# keyboard.net
KiCad netlist of a schematic drawn in Altium Designer
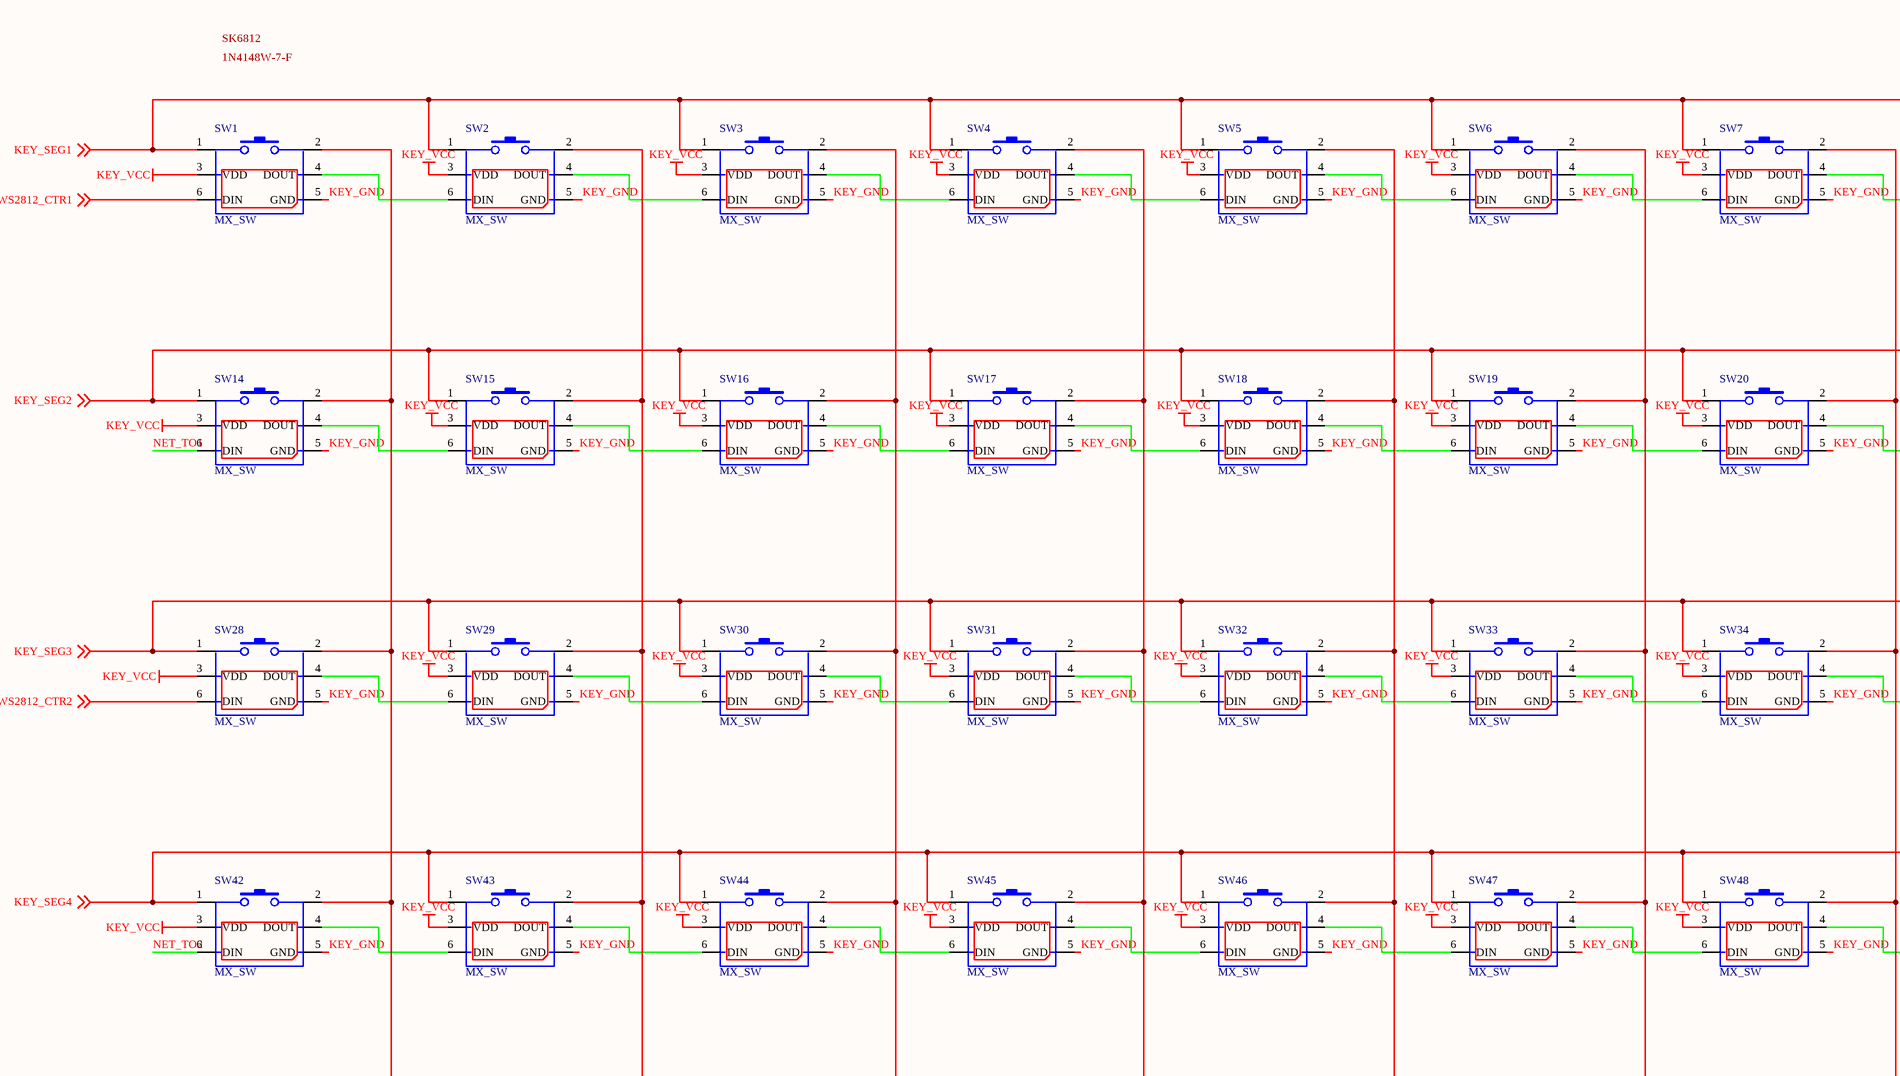
[diagram p0: keyboard.SchDoc, top left]
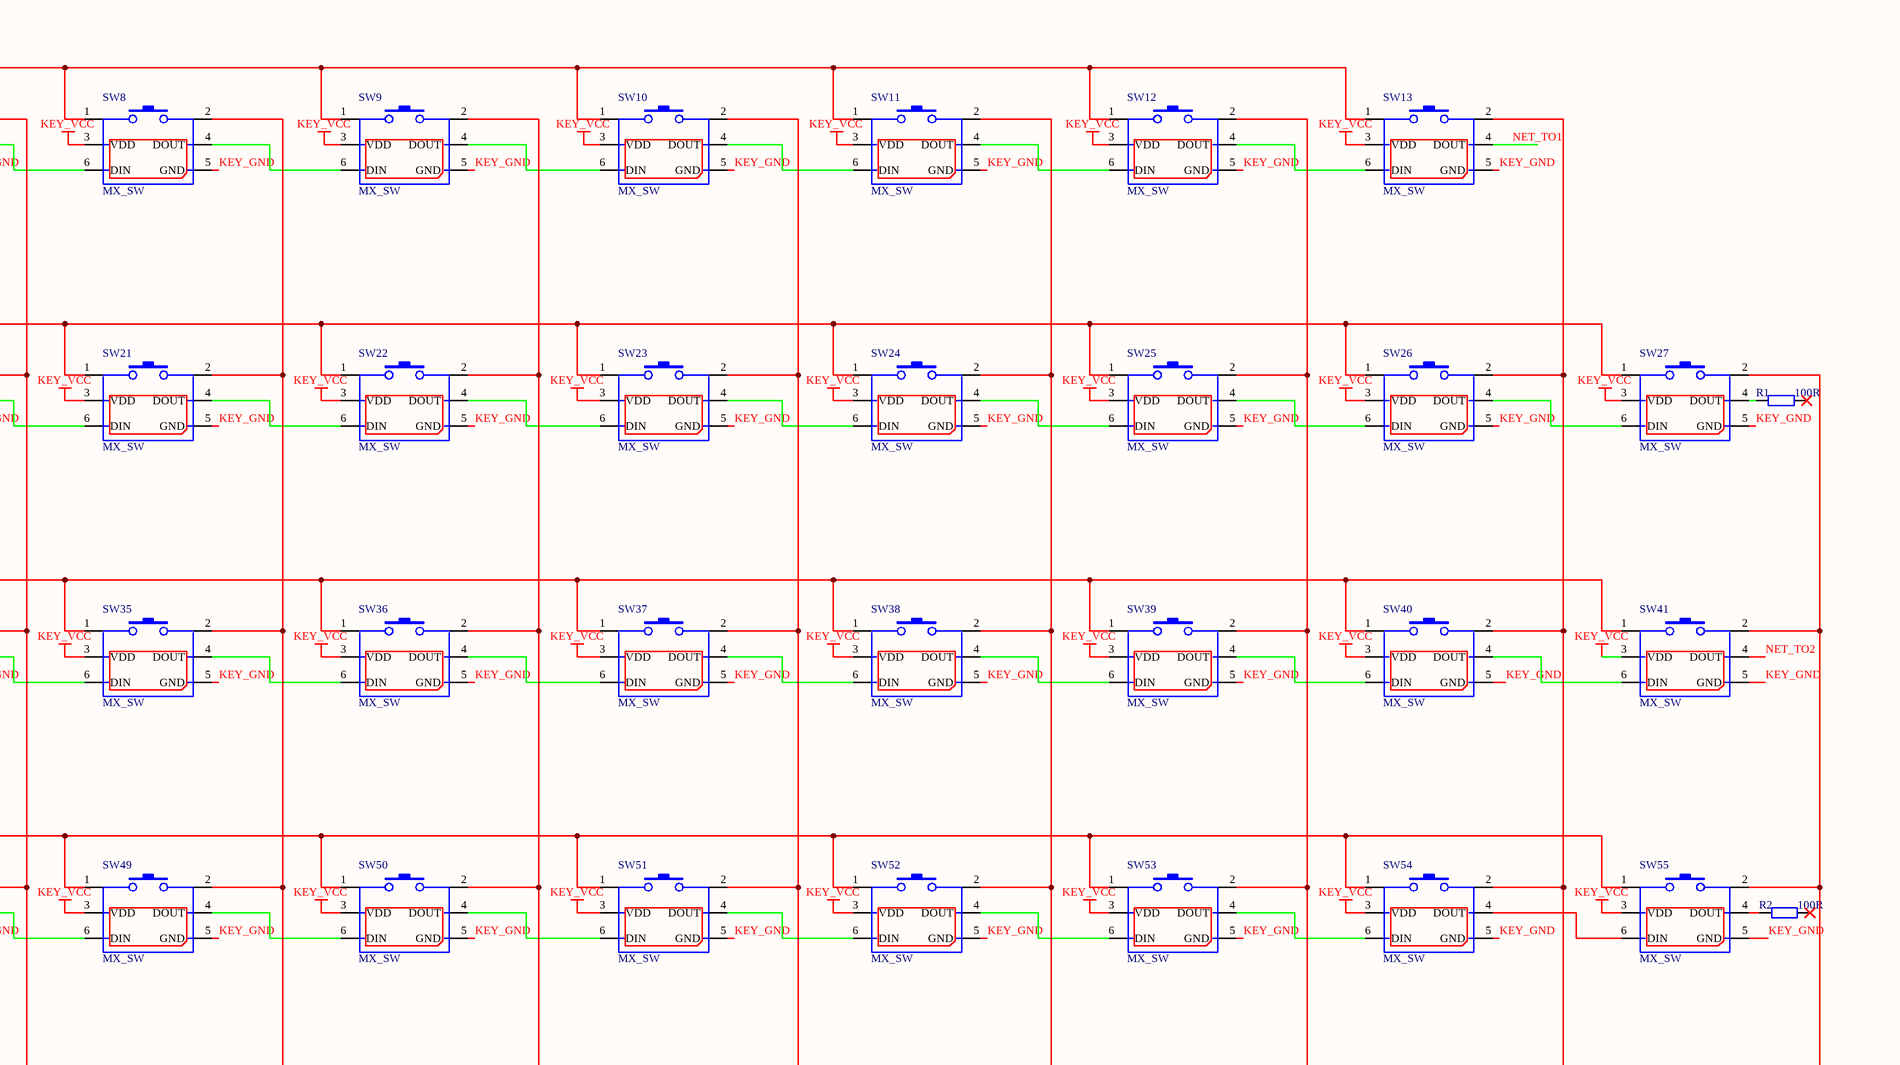
[diagram p1: keyboard.SchDoc, top right]
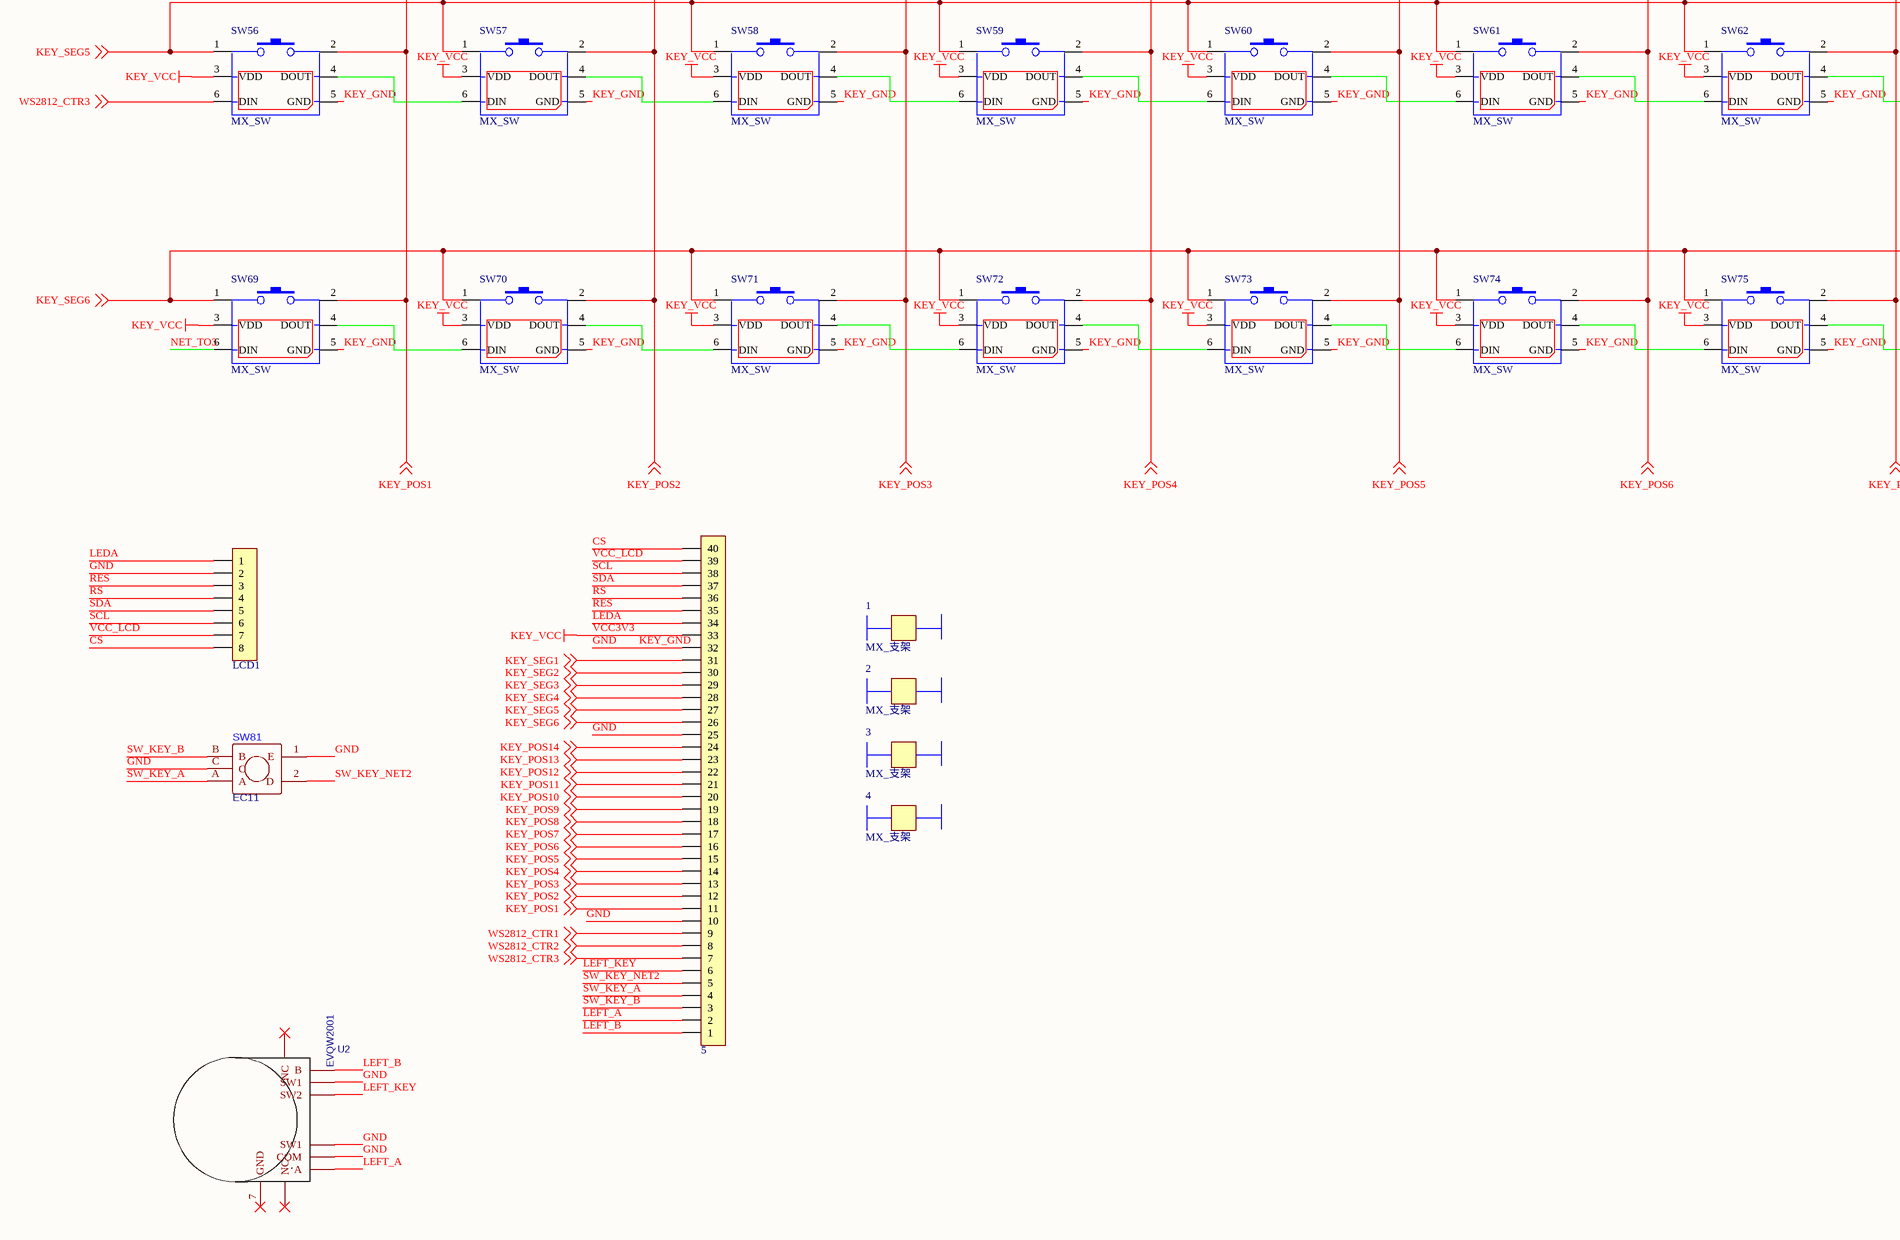
[diagram p2: keyboard.SchDoc, bottom left]
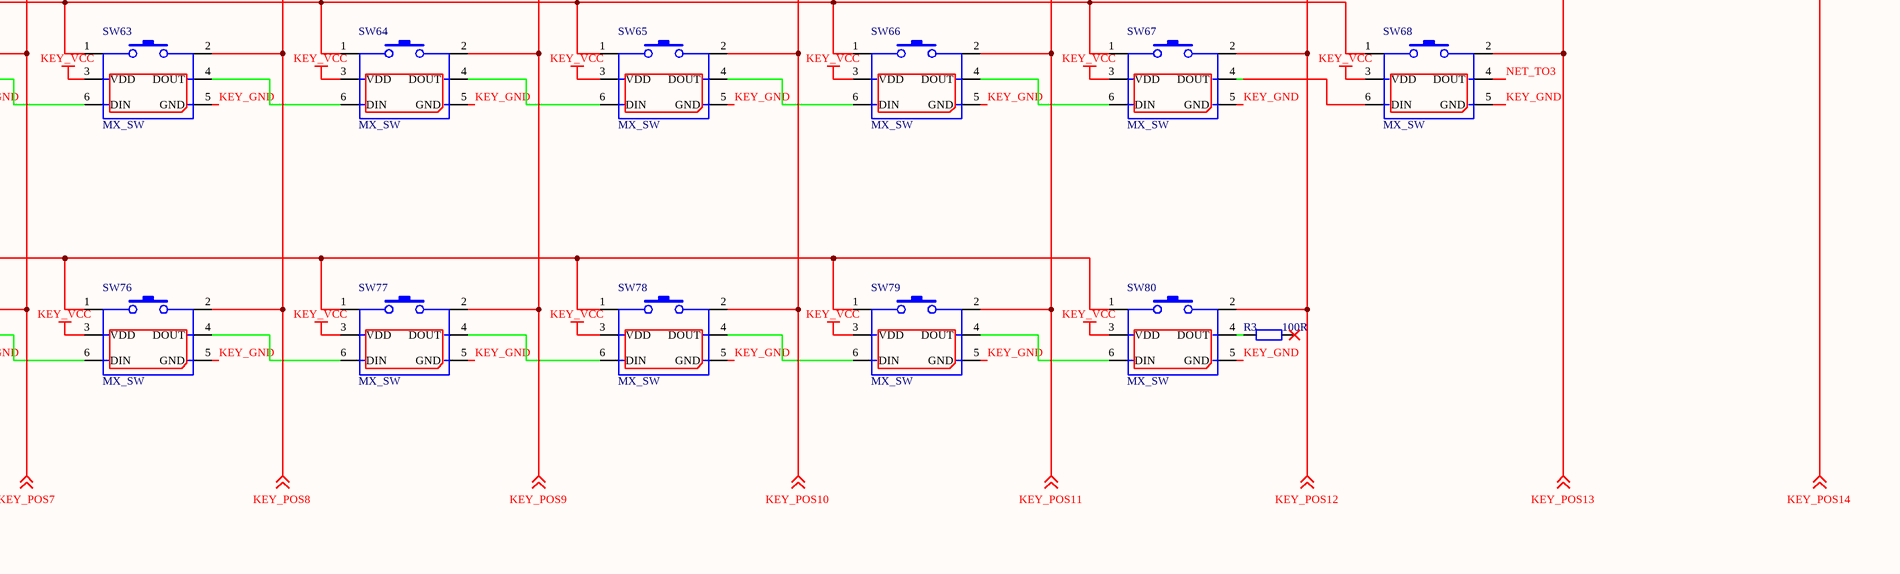
[diagram p3: keyboard.SchDoc, bottom right]

(export (version "E")
  (design (tool "Eeschema 10.0.6"))
  (components
    (comp (ref "1") (value "MX_支架") (footprint "1x2") (libsource (lib "机械键盘") (part "MX_支架")))
    (comp (ref "2") (value "MX_支架") (footprint "1x2") (libsource (lib "机械键盘") (part "MX_支架")))
    (comp (ref "3") (value "MX_支架") (footprint "1x2") (libsource (lib "机械键盘") (part "MX_支架")))
    (comp (ref "4") (value "MX_支架") (footprint "1x2") (libsource (lib "机械键盘") (part "MX_支架")))
    (comp (ref "5")
      (value "FPC1.0-40P")
      (footprint "FPC0.5 2H-WS-40P")
      (description "FPC连接器")
      (fields (field (name "版权归属") "黎明电子style"))
      (libsource (lib "FPC连接器") (part "FPC-40P"))
    )
    (comp (ref "LCD1")
      (value "FPC1.0-8P")
      (footprint "FPC0.5 2H-WS-8P")
      (description "FPC连接器")
      (fields (field (name "版权归属") "黎明电子style"))
      (libsource (lib "FPC连接器") (part "FPC-8P"))
    )
    (comp (ref "R1")
      (value "100R")
      (footprint "R 0805_M")
      (description "贴片电阻")
      (libsource (lib "0.1 - 电阻-电容-电感") (part "R"))
    )
    (comp (ref "R2")
      (value "100R")
      (footprint "R 0805_M")
      (description "贴片电阻")
      (libsource (lib "0.1 - 电阻-电容-电感") (part "R"))
    )
    (comp (ref "R3")
      (value "100R")
      (footprint "R 0805_M")
      (description "贴片电阻")
      (libsource (lib "0.1 - 电阻-电容-电感") (part "R"))
    )
    (comp (ref "SW1")
      (value "MX_SW")
      (footprint "MX_G_Pro")
      (description "with Fixation pins  1-Pole w/Diode")
      (libsource (lib "机械键盘") (part "MX_SW-7"))
    )
    (comp (ref "SW2")
      (value "MX_SW")
      (footprint "MX_G_Pro")
      (description "with Fixation pins  1-Pole w/Diode")
      (libsource (lib "机械键盘") (part "MX_SW-7"))
    )
    (comp (ref "SW3")
      (value "MX_SW")
      (footprint "MX_G_Pro")
      (description "with Fixation pins  1-Pole w/Diode")
      (libsource (lib "机械键盘") (part "MX_SW-7"))
    )
    (comp (ref "SW4")
      (value "MX_SW")
      (footprint "MX_G_Pro")
      (description "with Fixation pins  1-Pole w/Diode")
      (libsource (lib "机械键盘") (part "MX_SW-7"))
    )
    (comp (ref "SW5")
      (value "MX_SW")
      (footprint "MX_G_Pro")
      (description "with Fixation pins  1-Pole w/Diode")
      (libsource (lib "机械键盘") (part "MX_SW-7"))
    )
    (comp (ref "SW6")
      (value "MX_SW")
      (footprint "MX_G_Pro")
      (description "with Fixation pins  1-Pole w/Diode")
      (libsource (lib "机械键盘") (part "MX_SW-7"))
    )
    (comp (ref "SW7")
      (value "MX_SW")
      (footprint "MX_G_Pro")
      (description "with Fixation pins  1-Pole w/Diode")
      (libsource (lib "机械键盘") (part "MX_SW-7"))
    )
    (comp (ref "SW8")
      (value "MX_SW")
      (footprint "MX_G_Pro")
      (description "with Fixation pins  1-Pole w/Diode")
      (libsource (lib "机械键盘") (part "MX_SW-7"))
    )
    (comp (ref "SW9")
      (value "MX_SW")
      (footprint "MX_G_Pro")
      (description "with Fixation pins  1-Pole w/Diode")
      (libsource (lib "机械键盘") (part "MX_SW-7"))
    )
    (comp (ref "SW10")
      (value "MX_SW")
      (footprint "MX_G_Pro")
      (description "with Fixation pins  1-Pole w/Diode")
      (libsource (lib "机械键盘") (part "MX_SW-7"))
    )
    (comp (ref "SW11")
      (value "MX_SW")
      (footprint "MX_G_Pro")
      (description "with Fixation pins  1-Pole w/Diode")
      (libsource (lib "机械键盘") (part "MX_SW-7"))
    )
    (comp (ref "SW12")
      (value "MX_SW")
      (footprint "MX_G_Pro")
      (description "with Fixation pins  1-Pole w/Diode")
      (libsource (lib "机械键盘") (part "MX_SW-7"))
    )
    (comp (ref "SW13")
      (value "MX_SW")
      (footprint "MX_G_Pro")
      (description "with Fixation pins  1-Pole w/Diode")
      (libsource (lib "机械键盘") (part "MX_SW-7"))
    )
    (comp (ref "SW14")
      (value "MX_SW")
      (footprint "MX_G_Pro")
      (description "with Fixation pins  1-Pole w/Diode")
      (libsource (lib "机械键盘") (part "MX_SW-7"))
    )
    (comp (ref "SW15")
      (value "MX_SW")
      (footprint "MX_G_Pro")
      (description "with Fixation pins  1-Pole w/Diode")
      (libsource (lib "机械键盘") (part "MX_SW-7"))
    )
    (comp (ref "SW16")
      (value "MX_SW")
      (footprint "MX_G_Pro")
      (description "with Fixation pins  1-Pole w/Diode")
      (libsource (lib "机械键盘") (part "MX_SW-7"))
    )
    (comp (ref "SW17")
      (value "MX_SW")
      (footprint "MX_G_Pro")
      (description "with Fixation pins  1-Pole w/Diode")
      (libsource (lib "机械键盘") (part "MX_SW-7"))
    )
    (comp (ref "SW18")
      (value "MX_SW")
      (footprint "MX_G_Pro")
      (description "with Fixation pins  1-Pole w/Diode")
      (libsource (lib "机械键盘") (part "MX_SW-7"))
    )
    (comp (ref "SW19")
      (value "MX_SW")
      (footprint "MX_G_Pro")
      (description "with Fixation pins  1-Pole w/Diode")
      (libsource (lib "机械键盘") (part "MX_SW-7"))
    )
    (comp (ref "SW20")
      (value "MX_SW")
      (footprint "MX_G_Pro")
      (description "with Fixation pins  1-Pole w/Diode")
      (libsource (lib "机械键盘") (part "MX_SW-7"))
    )
    (comp (ref "SW21")
      (value "MX_SW")
      (footprint "MX_G_Pro")
      (description "with Fixation pins  1-Pole w/Diode")
      (libsource (lib "机械键盘") (part "MX_SW-7"))
    )
    (comp (ref "SW22")
      (value "MX_SW")
      (footprint "MX_G_Pro")
      (description "with Fixation pins  1-Pole w/Diode")
      (libsource (lib "机械键盘") (part "MX_SW-7"))
    )
    (comp (ref "SW23")
      (value "MX_SW")
      (footprint "MX_G_Pro")
      (description "with Fixation pins  1-Pole w/Diode")
      (libsource (lib "机械键盘") (part "MX_SW-7"))
    )
    (comp (ref "SW24")
      (value "MX_SW")
      (footprint "MX_G_Pro")
      (description "with Fixation pins  1-Pole w/Diode")
      (libsource (lib "机械键盘") (part "MX_SW-7"))
    )
    (comp (ref "SW25")
      (value "MX_SW")
      (footprint "MX_G_Pro")
      (description "with Fixation pins  1-Pole w/Diode")
      (libsource (lib "机械键盘") (part "MX_SW-7"))
    )
    (comp (ref "SW26")
      (value "MX_SW")
      (footprint "MX_G_Pro")
      (description "with Fixation pins  1-Pole w/Diode")
      (libsource (lib "机械键盘") (part "MX_SW-7"))
    )
    (comp (ref "SW27")
      (value "MX_SW")
      (footprint "MX_G_Pro_Backspace")
      (description "with Fixation pins  1-Pole w/Diode")
      (libsource (lib "机械键盘") (part "MX_SW-7"))
    )
    (comp (ref "SW28")
      (value "MX_SW")
      (footprint "MX_G_Pro_MX_Tab")
      (description "with Fixation pins  1-Pole w/Diode")
      (libsource (lib "机械键盘") (part "MX_SW-7"))
    )
    (comp (ref "SW29")
      (value "MX_SW")
      (footprint "MX_G_Pro")
      (description "with Fixation pins  1-Pole w/Diode")
      (libsource (lib "机械键盘") (part "MX_SW-7"))
    )
    (comp (ref "SW30")
      (value "MX_SW")
      (footprint "MX_G_Pro")
      (description "with Fixation pins  1-Pole w/Diode")
      (libsource (lib "机械键盘") (part "MX_SW-7"))
    )
    (comp (ref "SW31")
      (value "MX_SW")
      (footprint "MX_G_Pro")
      (description "with Fixation pins  1-Pole w/Diode")
      (libsource (lib "机械键盘") (part "MX_SW-7"))
    )
    (comp (ref "SW32")
      (value "MX_SW")
      (footprint "MX_G_Pro")
      (description "with Fixation pins  1-Pole w/Diode")
      (libsource (lib "机械键盘") (part "MX_SW-7"))
    )
    (comp (ref "SW33")
      (value "MX_SW")
      (footprint "MX_G_Pro")
      (description "with Fixation pins  1-Pole w/Diode")
      (libsource (lib "机械键盘") (part "MX_SW-7"))
    )
    (comp (ref "SW34")
      (value "MX_SW")
      (footprint "MX_G_Pro")
      (description "with Fixation pins  1-Pole w/Diode")
      (libsource (lib "机械键盘") (part "MX_SW-7"))
    )
    (comp (ref "SW35")
      (value "MX_SW")
      (footprint "MX_G_Pro")
      (description "with Fixation pins  1-Pole w/Diode")
      (libsource (lib "机械键盘") (part "MX_SW-7"))
    )
    (comp (ref "SW36")
      (value "MX_SW")
      (footprint "MX_G_Pro")
      (description "with Fixation pins  1-Pole w/Diode")
      (libsource (lib "机械键盘") (part "MX_SW-7"))
    )
    (comp (ref "SW37")
      (value "MX_SW")
      (footprint "MX_G_Pro")
      (description "with Fixation pins  1-Pole w/Diode")
      (libsource (lib "机械键盘") (part "MX_SW-7"))
    )
    (comp (ref "SW38")
      (value "MX_SW")
      (footprint "MX_G_Pro")
      (description "with Fixation pins  1-Pole w/Diode")
      (libsource (lib "机械键盘") (part "MX_SW-7"))
    )
    (comp (ref "SW39")
      (value "MX_SW")
      (footprint "MX_G_Pro")
      (description "with Fixation pins  1-Pole w/Diode")
      (libsource (lib "机械键盘") (part "MX_SW-7"))
    )
    (comp (ref "SW40")
      (value "MX_SW")
      (footprint "MX_G_Pro")
      (description "with Fixation pins  1-Pole w/Diode")
      (libsource (lib "机械键盘") (part "MX_SW-7"))
    )
    (comp (ref "SW41")
      (value "MX_SW")
      (footprint "MX_G_Pro_MX_Tab")
      (description "with Fixation pins  1-Pole w/Diode")
      (libsource (lib "机械键盘") (part "MX_SW-7"))
    )
    (comp (ref "SW42")
      (value "MX_SW")
      (footprint "MX_G_Pro_CapsLock")
      (description "with Fixation pins  1-Pole w/Diode")
      (libsource (lib "机械键盘") (part "MX_SW-7"))
    )
    (comp (ref "SW43")
      (value "MX_SW")
      (footprint "MX_G_Pro")
      (description "with Fixation pins  1-Pole w/Diode")
      (libsource (lib "机械键盘") (part "MX_SW-7"))
    )
    (comp (ref "SW44")
      (value "MX_SW")
      (footprint "MX_G_Pro")
      (description "with Fixation pins  1-Pole w/Diode")
      (libsource (lib "机械键盘") (part "MX_SW-7"))
    )
    (comp (ref "SW45")
      (value "MX_SW")
      (footprint "MX_G_Pro")
      (description "with Fixation pins  1-Pole w/Diode")
      (libsource (lib "机械键盘") (part "MX_SW-7"))
    )
    (comp (ref "SW46")
      (value "MX_SW")
      (footprint "MX_G_Pro")
      (description "with Fixation pins  1-Pole w/Diode")
      (libsource (lib "机械键盘") (part "MX_SW-7"))
    )
    (comp (ref "SW47")
      (value "MX_SW")
      (footprint "MX_G_Pro")
      (description "with Fixation pins  1-Pole w/Diode")
      (libsource (lib "机械键盘") (part "MX_SW-7"))
    )
    (comp (ref "SW48")
      (value "MX_SW")
      (footprint "MX_G_Pro")
      (description "with Fixation pins  1-Pole w/Diode")
      (libsource (lib "机械键盘") (part "MX_SW-7"))
    )
    (comp (ref "SW49")
      (value "MX_SW")
      (footprint "MX_G_Pro")
      (description "with Fixation pins  1-Pole w/Diode")
      (libsource (lib "机械键盘") (part "MX_SW-7"))
    )
    (comp (ref "SW50")
      (value "MX_SW")
      (footprint "MX_G_Pro")
      (description "with Fixation pins  1-Pole w/Diode")
      (libsource (lib "机械键盘") (part "MX_SW-7"))
    )
    (comp (ref "SW51")
      (value "MX_SW")
      (footprint "MX_G_Pro")
      (description "with Fixation pins  1-Pole w/Diode")
      (libsource (lib "机械键盘") (part "MX_SW-7"))
    )
    (comp (ref "SW52")
      (value "MX_SW")
      (footprint "MX_G_Pro")
      (description "with Fixation pins  1-Pole w/Diode")
      (libsource (lib "机械键盘") (part "MX_SW-7"))
    )
    (comp (ref "SW53")
      (value "MX_SW")
      (footprint "MX_G_Pro")
      (description "with Fixation pins  1-Pole w/Diode")
      (libsource (lib "机械键盘") (part "MX_SW-7"))
    )
    (comp (ref "SW54")
      (value "MX_SW")
      (footprint "MX_G_Pro_MX_左Shift(Enter)")
      (description "with Fixation pins  1-Pole w/Diode")
      (libsource (lib "机械键盘") (part "MX_SW-7"))
    )
    (comp (ref "SW55")
      (value "MX_SW")
      (footprint "MX_G_Pro")
      (description "with Fixation pins  1-Pole w/Diode")
      (libsource (lib "机械键盘") (part "MX_SW-7"))
    )
    (comp (ref "SW56")
      (value "MX_SW")
      (footprint "MX_G_Pro_MX_左Shift(Enter)")
      (description "with Fixation pins  1-Pole w/Diode")
      (libsource (lib "机械键盘") (part "MX_SW-7"))
    )
    (comp (ref "SW57")
      (value "MX_SW")
      (footprint "MX_G_Pro")
      (description "with Fixation pins  1-Pole w/Diode")
      (libsource (lib "机械键盘") (part "MX_SW-7"))
    )
    (comp (ref "SW58")
      (value "MX_SW")
      (footprint "MX_G_Pro")
      (description "with Fixation pins  1-Pole w/Diode")
      (libsource (lib "机械键盘") (part "MX_SW-7"))
    )
    (comp (ref "SW59")
      (value "MX_SW")
      (footprint "MX_G_Pro")
      (description "with Fixation pins  1-Pole w/Diode")
      (libsource (lib "机械键盘") (part "MX_SW-7"))
    )
    (comp (ref "SW60")
      (value "MX_SW")
      (footprint "MX_G_Pro")
      (description "with Fixation pins  1-Pole w/Diode")
      (libsource (lib "机械键盘") (part "MX_SW-7"))
    )
    (comp (ref "SW61")
      (value "MX_SW")
      (footprint "MX_G_Pro")
      (description "with Fixation pins  1-Pole w/Diode")
      (libsource (lib "机械键盘") (part "MX_SW-7"))
    )
    (comp (ref "SW62")
      (value "MX_SW")
      (footprint "MX_G_Pro")
      (description "with Fixation pins  1-Pole w/Diode")
      (libsource (lib "机械键盘") (part "MX_SW-7"))
    )
    (comp (ref "SW63")
      (value "MX_SW")
      (footprint "MX_G_Pro")
      (description "with Fixation pins  1-Pole w/Diode")
      (libsource (lib "机械键盘") (part "MX_SW-7"))
    )
    (comp (ref "SW64")
      (value "MX_SW")
      (footprint "MX_G_Pro")
      (description "with Fixation pins  1-Pole w/Diode")
      (libsource (lib "机械键盘") (part "MX_SW-7"))
    )
    (comp (ref "SW65")
      (value "MX_SW")
      (footprint "MX_G_Pro")
      (description "with Fixation pins  1-Pole w/Diode")
      (libsource (lib "机械键盘") (part "MX_SW-7"))
    )
    (comp (ref "SW66")
      (value "MX_SW")
      (footprint "MX_G_Pro")
      (description "with Fixation pins  1-Pole w/Diode")
      (libsource (lib "机械键盘") (part "MX_SW-7"))
    )
    (comp (ref "SW67")
      (value "MX_SW")
      (footprint "MX_G_Pro_MX_右Shift")
      (description "with Fixation pins  1-Pole w/Diode")
      (libsource (lib "机械键盘") (part "MX_SW-7"))
    )
    (comp (ref "SW68")
      (value "MX_SW")
      (footprint "MX_G_Pro")
      (description "with Fixation pins  1-Pole w/Diode")
      (libsource (lib "机械键盘") (part "MX_SW-7"))
    )
    (comp (ref "SW69")
      (value "MX_SW")
      (footprint "MX_G_Pro_Ctrl(Win)(Alt)")
      (description "with Fixation pins  1-Pole w/Diode")
      (libsource (lib "机械键盘") (part "MX_SW-7"))
    )
    (comp (ref "SW70")
      (value "MX_SW")
      (footprint "MX_G_Pro_Ctrl(Win)(Alt)")
      (description "with Fixation pins  1-Pole w/Diode")
      (libsource (lib "机械键盘") (part "MX_SW-7"))
    )
    (comp (ref "SW71")
      (value "MX_SW")
      (footprint "MX_G_Pro_Ctrl(Win)(Alt)")
      (description "with Fixation pins  1-Pole w/Diode")
      (libsource (lib "机械键盘") (part "MX_SW-7"))
    )
    (comp (ref "SW72")
      (value "MX_SW")
      (footprint "MX_G_Pro_MX_空格")
      (description "with Fixation pins  1-Pole w/Diode")
      (libsource (lib "机械键盘") (part "MX_SW-7"))
    )
    (comp (ref "SW73")
      (value "MX_SW")
      (footprint "MX_G_Pro_Ctrl(Win)(Alt)")
      (description "with Fixation pins  1-Pole w/Diode")
      (libsource (lib "机械键盘") (part "MX_SW-7"))
    )
    (comp (ref "SW74")
      (value "MX_SW")
      (footprint "MX_G_Pro_Ctrl(Win)(Alt)")
      (description "with Fixation pins  1-Pole w/Diode")
      (libsource (lib "机械键盘") (part "MX_SW-7"))
    )
    (comp (ref "SW75")
      (value "MX_SW")
      (footprint "MX_G_Pro_Ctrl(Win)(Alt)")
      (description "with Fixation pins  1-Pole w/Diode")
      (libsource (lib "机械键盘") (part "MX_SW-7"))
    )
    (comp (ref "SW76")
      (value "MX_SW")
      (footprint "MX_G_Pro_Ctrl(Win)(Alt)")
      (description "with Fixation pins  1-Pole w/Diode")
      (libsource (lib "机械键盘") (part "MX_SW-7"))
    )
    (comp (ref "SW77")
      (value "MX_SW")
      (footprint "MX_G_Pro")
      (description "with Fixation pins  1-Pole w/Diode")
      (libsource (lib "机械键盘") (part "MX_SW-7"))
    )
    (comp (ref "SW78")
      (value "MX_SW")
      (footprint "MX_G_Pro")
      (description "with Fixation pins  1-Pole w/Diode")
      (libsource (lib "机械键盘") (part "MX_SW-7"))
    )
    (comp (ref "SW79")
      (value "MX_SW")
      (footprint "MX_G_Pro")
      (description "with Fixation pins  1-Pole w/Diode")
      (libsource (lib "机械键盘") (part "MX_SW-7"))
    )
    (comp (ref "SW80")
      (value "MX_SW")
      (footprint "MX_G_Pro")
      (description "with Fixation pins  1-Pole w/Diode")
      (libsource (lib "机械键盘") (part "MX_SW-7"))
    )
    (comp (ref "SW81")
      (value "EC11")
      (footprint "BOURNS_PEC11R-4XXXF-SXXXX")
      (libsource (lib "机械键盘") (part "EC11"))
    )
    (comp (ref "U2")
      (value "EVQW2001")
      (footprint "EVQWK2001 - duplicate")
      (fields (field (name "CONTRIBUTOR") "jam_dan"))
      (libsource (lib "机械键盘") (part "EVQW2001"))
    )
  )
  (nets
    (net (code "1") (name "/CS") (class "Default")
      (node (ref "5") (pin "40") (pinfunction "40_40") (pintype "passive"))
      (node (ref "LCD1") (pin "8") (pinfunction "8_8") (pintype "passive"))
    )
    (net (code "2") (name "/GND") (class "Default")
      (node (ref "5") (pin "10") (pinfunction "10_10") (pintype "passive"))
      (node (ref "5") (pin "25") (pinfunction "25_25") (pintype "passive"))
      (node (ref "5") (pin "32") (pinfunction "32_32") (pintype "passive"))
      (node (ref "LCD1") (pin "2") (pinfunction "2_2") (pintype "passive"))
      (node (ref "SW1") (pin "5") (pinfunction "GND_5") (pintype "passive"))
      (node (ref "SW10") (pin "5") (pinfunction "GND_5") (pintype "passive"))
      (node (ref "SW11") (pin "5") (pinfunction "GND_5") (pintype "passive"))
      (node (ref "SW12") (pin "5") (pinfunction "GND_5") (pintype "passive"))
      (node (ref "SW13") (pin "5") (pinfunction "GND_5") (pintype "passive"))
      (node (ref "SW14") (pin "5") (pinfunction "GND_5") (pintype "passive"))
      (node (ref "SW15") (pin "5") (pinfunction "GND_5") (pintype "passive"))
      (node (ref "SW16") (pin "5") (pinfunction "GND_5") (pintype "passive"))
      (node (ref "SW17") (pin "5") (pinfunction "GND_5") (pintype "passive"))
      (node (ref "SW18") (pin "5") (pinfunction "GND_5") (pintype "passive"))
      (node (ref "SW19") (pin "5") (pinfunction "GND_5") (pintype "passive"))
      (node (ref "SW2") (pin "5") (pinfunction "GND_5") (pintype "passive"))
      (node (ref "SW20") (pin "5") (pinfunction "GND_5") (pintype "passive"))
      (node (ref "SW21") (pin "5") (pinfunction "GND_5") (pintype "passive"))
      (node (ref "SW22") (pin "5") (pinfunction "GND_5") (pintype "passive"))
      (node (ref "SW23") (pin "5") (pinfunction "GND_5") (pintype "passive"))
      (node (ref "SW24") (pin "5") (pinfunction "GND_5") (pintype "passive"))
      (node (ref "SW25") (pin "5") (pinfunction "GND_5") (pintype "passive"))
      (node (ref "SW26") (pin "5") (pinfunction "GND_5") (pintype "passive"))
      (node (ref "SW27") (pin "5") (pinfunction "GND_5") (pintype "passive"))
      (node (ref "SW28") (pin "5") (pinfunction "GND_5") (pintype "passive"))
      (node (ref "SW29") (pin "5") (pinfunction "GND_5") (pintype "passive"))
      (node (ref "SW3") (pin "5") (pinfunction "GND_5") (pintype "passive"))
      (node (ref "SW30") (pin "5") (pinfunction "GND_5") (pintype "passive"))
      (node (ref "SW31") (pin "5") (pinfunction "GND_5") (pintype "passive"))
      (node (ref "SW32") (pin "5") (pinfunction "GND_5") (pintype "passive"))
      (node (ref "SW33") (pin "5") (pinfunction "GND_5") (pintype "passive"))
      (node (ref "SW34") (pin "5") (pinfunction "GND_5") (pintype "passive"))
      (node (ref "SW35") (pin "5") (pinfunction "GND_5") (pintype "passive"))
      (node (ref "SW36") (pin "5") (pinfunction "GND_5") (pintype "passive"))
      (node (ref "SW37") (pin "5") (pinfunction "GND_5") (pintype "passive"))
      (node (ref "SW38") (pin "5") (pinfunction "GND_5") (pintype "passive"))
      (node (ref "SW39") (pin "5") (pinfunction "GND_5") (pintype "passive"))
      (node (ref "SW4") (pin "5") (pinfunction "GND_5") (pintype "passive"))
      (node (ref "SW40") (pin "5") (pinfunction "GND_5") (pintype "passive"))
      (node (ref "SW41") (pin "5") (pinfunction "GND_5") (pintype "passive"))
      (node (ref "SW42") (pin "5") (pinfunction "GND_5") (pintype "passive"))
      (node (ref "SW43") (pin "5") (pinfunction "GND_5") (pintype "passive"))
      (node (ref "SW44") (pin "5") (pinfunction "GND_5") (pintype "passive"))
      (node (ref "SW45") (pin "5") (pinfunction "GND_5") (pintype "passive"))
      (node (ref "SW46") (pin "5") (pinfunction "GND_5") (pintype "passive"))
      (node (ref "SW47") (pin "5") (pinfunction "GND_5") (pintype "passive"))
      (node (ref "SW48") (pin "5") (pinfunction "GND_5") (pintype "passive"))
      (node (ref "SW49") (pin "5") (pinfunction "GND_5") (pintype "passive"))
      (node (ref "SW5") (pin "5") (pinfunction "GND_5") (pintype "passive"))
      (node (ref "SW50") (pin "5") (pinfunction "GND_5") (pintype "passive"))
      (node (ref "SW51") (pin "5") (pinfunction "GND_5") (pintype "passive"))
      (node (ref "SW52") (pin "5") (pinfunction "GND_5") (pintype "passive"))
      (node (ref "SW53") (pin "5") (pinfunction "GND_5") (pintype "passive"))
      (node (ref "SW54") (pin "5") (pinfunction "GND_5") (pintype "passive"))
      (node (ref "SW55") (pin "5") (pinfunction "GND_5") (pintype "passive"))
      (node (ref "SW56") (pin "5") (pinfunction "GND_5") (pintype "passive"))
      (node (ref "SW57") (pin "5") (pinfunction "GND_5") (pintype "passive"))
      (node (ref "SW58") (pin "5") (pinfunction "GND_5") (pintype "passive"))
      (node (ref "SW59") (pin "5") (pinfunction "GND_5") (pintype "passive"))
      (node (ref "SW6") (pin "5") (pinfunction "GND_5") (pintype "passive"))
      (node (ref "SW60") (pin "5") (pinfunction "GND_5") (pintype "passive"))
      (node (ref "SW61") (pin "5") (pinfunction "GND_5") (pintype "passive"))
      (node (ref "SW62") (pin "5") (pinfunction "GND_5") (pintype "passive"))
      (node (ref "SW63") (pin "5") (pinfunction "GND_5") (pintype "passive"))
      (node (ref "SW64") (pin "5") (pinfunction "GND_5") (pintype "passive"))
      (node (ref "SW65") (pin "5") (pinfunction "GND_5") (pintype "passive"))
      (node (ref "SW66") (pin "5") (pinfunction "GND_5") (pintype "passive"))
      (node (ref "SW67") (pin "5") (pinfunction "GND_5") (pintype "passive"))
      (node (ref "SW68") (pin "5") (pinfunction "GND_5") (pintype "passive"))
      (node (ref "SW69") (pin "5") (pinfunction "GND_5") (pintype "passive"))
      (node (ref "SW7") (pin "5") (pinfunction "GND_5") (pintype "passive"))
      (node (ref "SW70") (pin "5") (pinfunction "GND_5") (pintype "passive"))
      (node (ref "SW71") (pin "5") (pinfunction "GND_5") (pintype "passive"))
      (node (ref "SW72") (pin "5") (pinfunction "GND_5") (pintype "passive"))
      (node (ref "SW73") (pin "5") (pinfunction "GND_5") (pintype "passive"))
      (node (ref "SW74") (pin "5") (pinfunction "GND_5") (pintype "passive"))
      (node (ref "SW75") (pin "5") (pinfunction "GND_5") (pintype "passive"))
      (node (ref "SW76") (pin "5") (pinfunction "GND_5") (pintype "passive"))
      (node (ref "SW77") (pin "5") (pinfunction "GND_5") (pintype "passive"))
      (node (ref "SW78") (pin "5") (pinfunction "GND_5") (pintype "passive"))
      (node (ref "SW79") (pin "5") (pinfunction "GND_5") (pintype "passive"))
      (node (ref "SW8") (pin "5") (pinfunction "GND_5") (pintype "passive"))
      (node (ref "SW80") (pin "5") (pinfunction "GND_5") (pintype "passive"))
      (node (ref "SW81") (pin "1") (pinfunction "E_1") (pintype "passive"))
      (node (ref "SW81") (pin "C") (pinfunction "C_C") (pintype "passive"))
      (node (ref "SW9") (pin "5") (pinfunction "GND_5") (pintype "passive"))
      (node (ref "U2") (pin "2") (pinfunction "SW1_2") (pintype "passive"))
      (node (ref "U2") (pin "4") (pinfunction "SW1_4") (pintype "passive"))
      (node (ref "U2") (pin "5") (pinfunction "COM_5") (pintype "passive"))
    )
    (net (code "3") (name "/LEDA") (class "Default")
      (node (ref "5") (pin "34") (pinfunction "34_34") (pintype "passive"))
      (node (ref "LCD1") (pin "1") (pinfunction "1_1") (pintype "passive"))
    )
    (net (code "4") (name "/LEFT_A") (class "Default")
      (node (ref "5") (pin "2") (pinfunction "2_2") (pintype "passive"))
      (node (ref "U2") (pin "6") (pinfunction "A_6") (pintype "passive"))
    )
    (net (code "5") (name "/LEFT_B") (class "Default")
      (node (ref "5") (pin "1") (pinfunction "1_1") (pintype "passive"))
      (node (ref "U2") (pin "1") (pinfunction "B_1") (pintype "passive"))
    )
    (net (code "6") (name "/LEFT_KEY") (class "Default")
      (node (ref "5") (pin "6") (pinfunction "6_6") (pintype "passive"))
      (node (ref "U2") (pin "3") (pinfunction "SW2_3") (pintype "passive"))
    )
    (net (code "7") (name "/NET_TO1") (class "Default")
      (node (ref "SW13") (pin "4") (pinfunction "DOUT_4") (pintype "passive"))
      (node (ref "SW14") (pin "6") (pinfunction "DIN_6") (pintype "passive"))
    )
    (net (code "8") (name "/NET_TO2") (class "Default")
      (node (ref "SW41") (pin "4") (pinfunction "DOUT_4") (pintype "passive"))
      (node (ref "SW42") (pin "6") (pinfunction "DIN_6") (pintype "passive"))
    )
    (net (code "9") (name "/NET_TO3") (class "Default")
      (node (ref "SW68") (pin "4") (pinfunction "DOUT_4") (pintype "passive"))
      (node (ref "SW69") (pin "6") (pinfunction "DIN_6") (pintype "passive"))
    )
    (net (code "10") (name "/RES") (class "Default")
      (node (ref "5") (pin "35") (pinfunction "35_35") (pintype "passive"))
      (node (ref "LCD1") (pin "3") (pinfunction "3_3") (pintype "passive"))
    )
    (net (code "11") (name "/RS") (class "Default")
      (node (ref "5") (pin "36") (pinfunction "36_36") (pintype "passive"))
      (node (ref "LCD1") (pin "4") (pinfunction "4_4") (pintype "passive"))
    )
    (net (code "12") (name "/SCL") (class "Default")
      (node (ref "5") (pin "38") (pinfunction "38_38") (pintype "passive"))
      (node (ref "LCD1") (pin "6") (pinfunction "6_6") (pintype "passive"))
    )
    (net (code "13") (name "/SDA") (class "Default")
      (node (ref "5") (pin "37") (pinfunction "37_37") (pintype "passive"))
      (node (ref "LCD1") (pin "5") (pinfunction "5_5") (pintype "passive"))
    )
    (net (code "14") (name "/SW_KEY_A") (class "Default")
      (node (ref "5") (pin "4") (pinfunction "4_4") (pintype "passive"))
      (node (ref "SW81") (pin "A") (pinfunction "A_A") (pintype "passive"))
    )
    (net (code "15") (name "/SW_KEY_B") (class "Default")
      (node (ref "5") (pin "3") (pinfunction "3_3") (pintype "passive"))
      (node (ref "SW81") (pin "B") (pinfunction "B_B") (pintype "passive"))
    )
    (net (code "16") (name "/SW_KEY_NET2") (class "Default")
      (node (ref "5") (pin "5") (pinfunction "5_5") (pintype "passive"))
      (node (ref "SW81") (pin "2") (pinfunction "D_2") (pintype "passive"))
    )
    (net (code "17") (name "/VCC_LCD") (class "Default")
      (node (ref "5") (pin "39") (pinfunction "39_39") (pintype "passive"))
      (node (ref "LCD1") (pin "7") (pinfunction "7_7") (pintype "passive"))
    )
    (net (code "18") (name "KEY_POS1") (class "Default")
      (node (ref "5") (pin "11") (pinfunction "11_11") (pintype "passive"))
      (node (ref "SW1") (pin "2") (pinfunction "2_2") (pintype "passive"))
      (node (ref "SW14") (pin "2") (pinfunction "2_2") (pintype "passive"))
      (node (ref "SW28") (pin "2") (pinfunction "2_2") (pintype "passive"))
      (node (ref "SW42") (pin "2") (pinfunction "2_2") (pintype "passive"))
      (node (ref "SW56") (pin "2") (pinfunction "2_2") (pintype "passive"))
      (node (ref "SW69") (pin "2") (pinfunction "2_2") (pintype "passive"))
    )
    (net (code "19") (name "KEY_POS2") (class "Default")
      (node (ref "5") (pin "12") (pinfunction "12_12") (pintype "passive"))
      (node (ref "SW15") (pin "2") (pinfunction "2_2") (pintype "passive"))
      (node (ref "SW2") (pin "2") (pinfunction "2_2") (pintype "passive"))
      (node (ref "SW29") (pin "2") (pinfunction "2_2") (pintype "passive"))
      (node (ref "SW43") (pin "2") (pinfunction "2_2") (pintype "passive"))
      (node (ref "SW57") (pin "2") (pinfunction "2_2") (pintype "passive"))
      (node (ref "SW70") (pin "2") (pinfunction "2_2") (pintype "passive"))
    )
    (net (code "20") (name "KEY_POS3") (class "Default")
      (node (ref "5") (pin "13") (pinfunction "13_13") (pintype "passive"))
      (node (ref "SW16") (pin "2") (pinfunction "2_2") (pintype "passive"))
      (node (ref "SW3") (pin "2") (pinfunction "2_2") (pintype "passive"))
      (node (ref "SW30") (pin "2") (pinfunction "2_2") (pintype "passive"))
      (node (ref "SW44") (pin "2") (pinfunction "2_2") (pintype "passive"))
      (node (ref "SW58") (pin "2") (pinfunction "2_2") (pintype "passive"))
      (node (ref "SW71") (pin "2") (pinfunction "2_2") (pintype "passive"))
    )
    (net (code "21") (name "KEY_POS4") (class "Default")
      (node (ref "5") (pin "14") (pinfunction "14_14") (pintype "passive"))
      (node (ref "SW17") (pin "2") (pinfunction "2_2") (pintype "passive"))
      (node (ref "SW31") (pin "2") (pinfunction "2_2") (pintype "passive"))
      (node (ref "SW4") (pin "2") (pinfunction "2_2") (pintype "passive"))
      (node (ref "SW45") (pin "2") (pinfunction "2_2") (pintype "passive"))
      (node (ref "SW59") (pin "2") (pinfunction "2_2") (pintype "passive"))
      (node (ref "SW72") (pin "2") (pinfunction "2_2") (pintype "passive"))
    )
    (net (code "22") (name "KEY_POS5") (class "Default")
      (node (ref "5") (pin "15") (pinfunction "15_15") (pintype "passive"))
      (node (ref "SW18") (pin "2") (pinfunction "2_2") (pintype "passive"))
      (node (ref "SW32") (pin "2") (pinfunction "2_2") (pintype "passive"))
      (node (ref "SW46") (pin "2") (pinfunction "2_2") (pintype "passive"))
      (node (ref "SW5") (pin "2") (pinfunction "2_2") (pintype "passive"))
      (node (ref "SW60") (pin "2") (pinfunction "2_2") (pintype "passive"))
      (node (ref "SW73") (pin "2") (pinfunction "2_2") (pintype "passive"))
    )
    (net (code "23") (name "KEY_POS6") (class "Default")
      (node (ref "5") (pin "16") (pinfunction "16_16") (pintype "passive"))
      (node (ref "SW19") (pin "2") (pinfunction "2_2") (pintype "passive"))
      (node (ref "SW33") (pin "2") (pinfunction "2_2") (pintype "passive"))
      (node (ref "SW47") (pin "2") (pinfunction "2_2") (pintype "passive"))
      (node (ref "SW6") (pin "2") (pinfunction "2_2") (pintype "passive"))
      (node (ref "SW61") (pin "2") (pinfunction "2_2") (pintype "passive"))
      (node (ref "SW74") (pin "2") (pinfunction "2_2") (pintype "passive"))
    )
    (net (code "24") (name "KEY_POS7") (class "Default")
      (node (ref "5") (pin "17") (pinfunction "17_17") (pintype "passive"))
      (node (ref "SW20") (pin "2") (pinfunction "2_2") (pintype "passive"))
      (node (ref "SW34") (pin "2") (pinfunction "2_2") (pintype "passive"))
      (node (ref "SW48") (pin "2") (pinfunction "2_2") (pintype "passive"))
      (node (ref "SW62") (pin "2") (pinfunction "2_2") (pintype "passive"))
      (node (ref "SW7") (pin "2") (pinfunction "2_2") (pintype "passive"))
      (node (ref "SW75") (pin "2") (pinfunction "2_2") (pintype "passive"))
    )
    (net (code "25") (name "KEY_POS8") (class "Default")
      (node (ref "5") (pin "18") (pinfunction "18_18") (pintype "passive"))
      (node (ref "SW21") (pin "2") (pinfunction "2_2") (pintype "passive"))
      (node (ref "SW35") (pin "2") (pinfunction "2_2") (pintype "passive"))
      (node (ref "SW49") (pin "2") (pinfunction "2_2") (pintype "passive"))
      (node (ref "SW63") (pin "2") (pinfunction "2_2") (pintype "passive"))
      (node (ref "SW76") (pin "2") (pinfunction "2_2") (pintype "passive"))
      (node (ref "SW8") (pin "2") (pinfunction "2_2") (pintype "passive"))
    )
    (net (code "26") (name "KEY_POS9") (class "Default")
      (node (ref "5") (pin "19") (pinfunction "19_19") (pintype "passive"))
      (node (ref "SW22") (pin "2") (pinfunction "2_2") (pintype "passive"))
      (node (ref "SW36") (pin "2") (pinfunction "2_2") (pintype "passive"))
      (node (ref "SW50") (pin "2") (pinfunction "2_2") (pintype "passive"))
      (node (ref "SW64") (pin "2") (pinfunction "2_2") (pintype "passive"))
      (node (ref "SW77") (pin "2") (pinfunction "2_2") (pintype "passive"))
      (node (ref "SW9") (pin "2") (pinfunction "2_2") (pintype "passive"))
    )
    (net (code "27") (name "KEY_POS10") (class "Default")
      (node (ref "5") (pin "20") (pinfunction "20_20") (pintype "passive"))
      (node (ref "SW10") (pin "2") (pinfunction "2_2") (pintype "passive"))
      (node (ref "SW23") (pin "2") (pinfunction "2_2") (pintype "passive"))
      (node (ref "SW37") (pin "2") (pinfunction "2_2") (pintype "passive"))
      (node (ref "SW51") (pin "2") (pinfunction "2_2") (pintype "passive"))
      (node (ref "SW65") (pin "2") (pinfunction "2_2") (pintype "passive"))
      (node (ref "SW78") (pin "2") (pinfunction "2_2") (pintype "passive"))
    )
    (net (code "28") (name "KEY_POS11") (class "Default")
      (node (ref "5") (pin "21") (pinfunction "21_21") (pintype "passive"))
      (node (ref "SW11") (pin "2") (pinfunction "2_2") (pintype "passive"))
      (node (ref "SW24") (pin "2") (pinfunction "2_2") (pintype "passive"))
      (node (ref "SW38") (pin "2") (pinfunction "2_2") (pintype "passive"))
      (node (ref "SW52") (pin "2") (pinfunction "2_2") (pintype "passive"))
      (node (ref "SW66") (pin "2") (pinfunction "2_2") (pintype "passive"))
      (node (ref "SW79") (pin "2") (pinfunction "2_2") (pintype "passive"))
    )
    (net (code "29") (name "KEY_POS12") (class "Default")
      (node (ref "5") (pin "22") (pinfunction "22_22") (pintype "passive"))
      (node (ref "SW12") (pin "2") (pinfunction "2_2") (pintype "passive"))
      (node (ref "SW25") (pin "2") (pinfunction "2_2") (pintype "passive"))
      (node (ref "SW39") (pin "2") (pinfunction "2_2") (pintype "passive"))
      (node (ref "SW53") (pin "2") (pinfunction "2_2") (pintype "passive"))
      (node (ref "SW67") (pin "2") (pinfunction "2_2") (pintype "passive"))
      (node (ref "SW80") (pin "2") (pinfunction "2_2") (pintype "passive"))
    )
    (net (code "30") (name "KEY_POS13") (class "Default")
      (node (ref "5") (pin "23") (pinfunction "23_23") (pintype "passive"))
      (node (ref "SW13") (pin "2") (pinfunction "2_2") (pintype "passive"))
      (node (ref "SW26") (pin "2") (pinfunction "2_2") (pintype "passive"))
      (node (ref "SW40") (pin "2") (pinfunction "2_2") (pintype "passive"))
      (node (ref "SW54") (pin "2") (pinfunction "2_2") (pintype "passive"))
      (node (ref "SW68") (pin "2") (pinfunction "2_2") (pintype "passive"))
    )
    (net (code "31") (name "KEY_POS14") (class "Default")
      (node (ref "5") (pin "24") (pinfunction "24_24") (pintype "passive"))
      (node (ref "SW27") (pin "2") (pinfunction "2_2") (pintype "passive"))
      (node (ref "SW41") (pin "2") (pinfunction "2_2") (pintype "passive"))
      (node (ref "SW55") (pin "2") (pinfunction "2_2") (pintype "passive"))
    )
    (net (code "32") (name "KEY_SEG1") (class "Default")
      (node (ref "5") (pin "31") (pinfunction "31_31") (pintype "passive"))
      (node (ref "SW1") (pin "1") (pinfunction "1_1") (pintype "passive"))
      (node (ref "SW10") (pin "1") (pinfunction "1_1") (pintype "passive"))
      (node (ref "SW11") (pin "1") (pinfunction "1_1") (pintype "passive"))
      (node (ref "SW12") (pin "1") (pinfunction "1_1") (pintype "passive"))
      (node (ref "SW13") (pin "1") (pinfunction "1_1") (pintype "passive"))
      (node (ref "SW2") (pin "1") (pinfunction "1_1") (pintype "passive"))
      (node (ref "SW3") (pin "1") (pinfunction "1_1") (pintype "passive"))
      (node (ref "SW4") (pin "1") (pinfunction "1_1") (pintype "passive"))
      (node (ref "SW5") (pin "1") (pinfunction "1_1") (pintype "passive"))
      (node (ref "SW6") (pin "1") (pinfunction "1_1") (pintype "passive"))
      (node (ref "SW7") (pin "1") (pinfunction "1_1") (pintype "passive"))
      (node (ref "SW8") (pin "1") (pinfunction "1_1") (pintype "passive"))
      (node (ref "SW9") (pin "1") (pinfunction "1_1") (pintype "passive"))
    )
    (net (code "33") (name "KEY_SEG2") (class "Default")
      (node (ref "5") (pin "30") (pinfunction "30_30") (pintype "passive"))
      (node (ref "SW14") (pin "1") (pinfunction "1_1") (pintype "passive"))
      (node (ref "SW15") (pin "1") (pinfunction "1_1") (pintype "passive"))
      (node (ref "SW16") (pin "1") (pinfunction "1_1") (pintype "passive"))
      (node (ref "SW17") (pin "1") (pinfunction "1_1") (pintype "passive"))
      (node (ref "SW18") (pin "1") (pinfunction "1_1") (pintype "passive"))
      (node (ref "SW19") (pin "1") (pinfunction "1_1") (pintype "passive"))
      (node (ref "SW20") (pin "1") (pinfunction "1_1") (pintype "passive"))
      (node (ref "SW21") (pin "1") (pinfunction "1_1") (pintype "passive"))
      (node (ref "SW22") (pin "1") (pinfunction "1_1") (pintype "passive"))
      (node (ref "SW23") (pin "1") (pinfunction "1_1") (pintype "passive"))
      (node (ref "SW24") (pin "1") (pinfunction "1_1") (pintype "passive"))
      (node (ref "SW25") (pin "1") (pinfunction "1_1") (pintype "passive"))
      (node (ref "SW26") (pin "1") (pinfunction "1_1") (pintype "passive"))
      (node (ref "SW27") (pin "1") (pinfunction "1_1") (pintype "passive"))
    )
    (net (code "34") (name "KEY_SEG3") (class "Default")
      (node (ref "5") (pin "29") (pinfunction "29_29") (pintype "passive"))
      (node (ref "SW28") (pin "1") (pinfunction "1_1") (pintype "passive"))
      (node (ref "SW29") (pin "1") (pinfunction "1_1") (pintype "passive"))
      (node (ref "SW30") (pin "1") (pinfunction "1_1") (pintype "passive"))
      (node (ref "SW31") (pin "1") (pinfunction "1_1") (pintype "passive"))
      (node (ref "SW32") (pin "1") (pinfunction "1_1") (pintype "passive"))
      (node (ref "SW33") (pin "1") (pinfunction "1_1") (pintype "passive"))
      (node (ref "SW34") (pin "1") (pinfunction "1_1") (pintype "passive"))
      (node (ref "SW35") (pin "1") (pinfunction "1_1") (pintype "passive"))
      (node (ref "SW36") (pin "1") (pinfunction "1_1") (pintype "passive"))
      (node (ref "SW37") (pin "1") (pinfunction "1_1") (pintype "passive"))
      (node (ref "SW38") (pin "1") (pinfunction "1_1") (pintype "passive"))
      (node (ref "SW39") (pin "1") (pinfunction "1_1") (pintype "passive"))
      (node (ref "SW40") (pin "1") (pinfunction "1_1") (pintype "passive"))
      (node (ref "SW41") (pin "1") (pinfunction "1_1") (pintype "passive"))
    )
    (net (code "35") (name "KEY_SEG4") (class "Default")
      (node (ref "5") (pin "28") (pinfunction "28_28") (pintype "passive"))
      (node (ref "SW42") (pin "1") (pinfunction "1_1") (pintype "passive"))
      (node (ref "SW43") (pin "1") (pinfunction "1_1") (pintype "passive"))
      (node (ref "SW44") (pin "1") (pinfunction "1_1") (pintype "passive"))
      (node (ref "SW45") (pin "1") (pinfunction "1_1") (pintype "passive"))
      (node (ref "SW46") (pin "1") (pinfunction "1_1") (pintype "passive"))
      (node (ref "SW47") (pin "1") (pinfunction "1_1") (pintype "passive"))
      (node (ref "SW48") (pin "1") (pinfunction "1_1") (pintype "passive"))
      (node (ref "SW49") (pin "1") (pinfunction "1_1") (pintype "passive"))
      (node (ref "SW50") (pin "1") (pinfunction "1_1") (pintype "passive"))
      (node (ref "SW51") (pin "1") (pinfunction "1_1") (pintype "passive"))
      (node (ref "SW52") (pin "1") (pinfunction "1_1") (pintype "passive"))
      (node (ref "SW53") (pin "1") (pinfunction "1_1") (pintype "passive"))
      (node (ref "SW54") (pin "1") (pinfunction "1_1") (pintype "passive"))
      (node (ref "SW55") (pin "1") (pinfunction "1_1") (pintype "passive"))
    )
    (net (code "36") (name "KEY_SEG5") (class "Default")
      (node (ref "5") (pin "27") (pinfunction "27_27") (pintype "passive"))
      (node (ref "SW56") (pin "1") (pinfunction "1_1") (pintype "passive"))
      (node (ref "SW57") (pin "1") (pinfunction "1_1") (pintype "passive"))
      (node (ref "SW58") (pin "1") (pinfunction "1_1") (pintype "passive"))
      (node (ref "SW59") (pin "1") (pinfunction "1_1") (pintype "passive"))
      (node (ref "SW60") (pin "1") (pinfunction "1_1") (pintype "passive"))
      (node (ref "SW61") (pin "1") (pinfunction "1_1") (pintype "passive"))
      (node (ref "SW62") (pin "1") (pinfunction "1_1") (pintype "passive"))
      (node (ref "SW63") (pin "1") (pinfunction "1_1") (pintype "passive"))
      (node (ref "SW64") (pin "1") (pinfunction "1_1") (pintype "passive"))
      (node (ref "SW65") (pin "1") (pinfunction "1_1") (pintype "passive"))
      (node (ref "SW66") (pin "1") (pinfunction "1_1") (pintype "passive"))
      (node (ref "SW67") (pin "1") (pinfunction "1_1") (pintype "passive"))
      (node (ref "SW68") (pin "1") (pinfunction "1_1") (pintype "passive"))
    )
    (net (code "37") (name "KEY_SEG6") (class "Default")
      (node (ref "5") (pin "26") (pinfunction "26_26") (pintype "passive"))
      (node (ref "SW69") (pin "1") (pinfunction "1_1") (pintype "passive"))
      (node (ref "SW70") (pin "1") (pinfunction "1_1") (pintype "passive"))
      (node (ref "SW71") (pin "1") (pinfunction "1_1") (pintype "passive"))
      (node (ref "SW72") (pin "1") (pinfunction "1_1") (pintype "passive"))
      (node (ref "SW73") (pin "1") (pinfunction "1_1") (pintype "passive"))
      (node (ref "SW74") (pin "1") (pinfunction "1_1") (pintype "passive"))
      (node (ref "SW75") (pin "1") (pinfunction "1_1") (pintype "passive"))
      (node (ref "SW76") (pin "1") (pinfunction "1_1") (pintype "passive"))
      (node (ref "SW77") (pin "1") (pinfunction "1_1") (pintype "passive"))
      (node (ref "SW78") (pin "1") (pinfunction "1_1") (pintype "passive"))
      (node (ref "SW79") (pin "1") (pinfunction "1_1") (pintype "passive"))
      (node (ref "SW80") (pin "1") (pinfunction "1_1") (pintype "passive"))
    )
    (net (code "38") (name "KEY_VCC") (class "Default")
      (node (ref "5") (pin "33") (pinfunction "33_33") (pintype "passive"))
      (node (ref "SW1") (pin "3") (pinfunction "VDD_3") (pintype "passive"))
      (node (ref "SW10") (pin "3") (pinfunction "VDD_3") (pintype "passive"))
      (node (ref "SW11") (pin "3") (pinfunction "VDD_3") (pintype "passive"))
      (node (ref "SW12") (pin "3") (pinfunction "VDD_3") (pintype "passive"))
      (node (ref "SW13") (pin "3") (pinfunction "VDD_3") (pintype "passive"))
      (node (ref "SW14") (pin "3") (pinfunction "VDD_3") (pintype "passive"))
      (node (ref "SW15") (pin "3") (pinfunction "VDD_3") (pintype "passive"))
      (node (ref "SW16") (pin "3") (pinfunction "VDD_3") (pintype "passive"))
      (node (ref "SW17") (pin "3") (pinfunction "VDD_3") (pintype "passive"))
      (node (ref "SW18") (pin "3") (pinfunction "VDD_3") (pintype "passive"))
      (node (ref "SW19") (pin "3") (pinfunction "VDD_3") (pintype "passive"))
      (node (ref "SW2") (pin "3") (pinfunction "VDD_3") (pintype "passive"))
      (node (ref "SW20") (pin "3") (pinfunction "VDD_3") (pintype "passive"))
      (node (ref "SW21") (pin "3") (pinfunction "VDD_3") (pintype "passive"))
      (node (ref "SW22") (pin "3") (pinfunction "VDD_3") (pintype "passive"))
      (node (ref "SW23") (pin "3") (pinfunction "VDD_3") (pintype "passive"))
      (node (ref "SW24") (pin "3") (pinfunction "VDD_3") (pintype "passive"))
      (node (ref "SW25") (pin "3") (pinfunction "VDD_3") (pintype "passive"))
      (node (ref "SW26") (pin "3") (pinfunction "VDD_3") (pintype "passive"))
      (node (ref "SW27") (pin "3") (pinfunction "VDD_3") (pintype "passive"))
      (node (ref "SW28") (pin "3") (pinfunction "VDD_3") (pintype "passive"))
      (node (ref "SW29") (pin "3") (pinfunction "VDD_3") (pintype "passive"))
      (node (ref "SW3") (pin "3") (pinfunction "VDD_3") (pintype "passive"))
      (node (ref "SW30") (pin "3") (pinfunction "VDD_3") (pintype "passive"))
      (node (ref "SW31") (pin "3") (pinfunction "VDD_3") (pintype "passive"))
      (node (ref "SW32") (pin "3") (pinfunction "VDD_3") (pintype "passive"))
      (node (ref "SW33") (pin "3") (pinfunction "VDD_3") (pintype "passive"))
      (node (ref "SW34") (pin "3") (pinfunction "VDD_3") (pintype "passive"))
      (node (ref "SW35") (pin "3") (pinfunction "VDD_3") (pintype "passive"))
      (node (ref "SW36") (pin "3") (pinfunction "VDD_3") (pintype "passive"))
      (node (ref "SW37") (pin "3") (pinfunction "VDD_3") (pintype "passive"))
      (node (ref "SW38") (pin "3") (pinfunction "VDD_3") (pintype "passive"))
      (node (ref "SW39") (pin "3") (pinfunction "VDD_3") (pintype "passive"))
      (node (ref "SW4") (pin "3") (pinfunction "VDD_3") (pintype "passive"))
      (node (ref "SW40") (pin "3") (pinfunction "VDD_3") (pintype "passive"))
      (node (ref "SW41") (pin "3") (pinfunction "VDD_3") (pintype "passive"))
      (node (ref "SW42") (pin "3") (pinfunction "VDD_3") (pintype "passive"))
      (node (ref "SW43") (pin "3") (pinfunction "VDD_3") (pintype "passive"))
      (node (ref "SW44") (pin "3") (pinfunction "VDD_3") (pintype "passive"))
      (node (ref "SW45") (pin "3") (pinfunction "VDD_3") (pintype "passive"))
      (node (ref "SW46") (pin "3") (pinfunction "VDD_3") (pintype "passive"))
      (node (ref "SW47") (pin "3") (pinfunction "VDD_3") (pintype "passive"))
      (node (ref "SW48") (pin "3") (pinfunction "VDD_3") (pintype "passive"))
      (node (ref "SW49") (pin "3") (pinfunction "VDD_3") (pintype "passive"))
      (node (ref "SW5") (pin "3") (pinfunction "VDD_3") (pintype "passive"))
      (node (ref "SW50") (pin "3") (pinfunction "VDD_3") (pintype "passive"))
      (node (ref "SW51") (pin "3") (pinfunction "VDD_3") (pintype "passive"))
      (node (ref "SW52") (pin "3") (pinfunction "VDD_3") (pintype "passive"))
      (node (ref "SW53") (pin "3") (pinfunction "VDD_3") (pintype "passive"))
      (node (ref "SW54") (pin "3") (pinfunction "VDD_3") (pintype "passive"))
      (node (ref "SW55") (pin "3") (pinfunction "VDD_3") (pintype "passive"))
      (node (ref "SW56") (pin "3") (pinfunction "VDD_3") (pintype "passive"))
      (node (ref "SW57") (pin "3") (pinfunction "VDD_3") (pintype "passive"))
      (node (ref "SW58") (pin "3") (pinfunction "VDD_3") (pintype "passive"))
      (node (ref "SW59") (pin "3") (pinfunction "VDD_3") (pintype "passive"))
      (node (ref "SW6") (pin "3") (pinfunction "VDD_3") (pintype "passive"))
      (node (ref "SW60") (pin "3") (pinfunction "VDD_3") (pintype "passive"))
      (node (ref "SW61") (pin "3") (pinfunction "VDD_3") (pintype "passive"))
      (node (ref "SW62") (pin "3") (pinfunction "VDD_3") (pintype "passive"))
      (node (ref "SW63") (pin "3") (pinfunction "VDD_3") (pintype "passive"))
      (node (ref "SW64") (pin "3") (pinfunction "VDD_3") (pintype "passive"))
      (node (ref "SW65") (pin "3") (pinfunction "VDD_3") (pintype "passive"))
      (node (ref "SW66") (pin "3") (pinfunction "VDD_3") (pintype "passive"))
      (node (ref "SW67") (pin "3") (pinfunction "VDD_3") (pintype "passive"))
      (node (ref "SW68") (pin "3") (pinfunction "VDD_3") (pintype "passive"))
      (node (ref "SW69") (pin "3") (pinfunction "VDD_3") (pintype "passive"))
      (node (ref "SW7") (pin "3") (pinfunction "VDD_3") (pintype "passive"))
      (node (ref "SW70") (pin "3") (pinfunction "VDD_3") (pintype "passive"))
      (node (ref "SW71") (pin "3") (pinfunction "VDD_3") (pintype "passive"))
      (node (ref "SW72") (pin "3") (pinfunction "VDD_3") (pintype "passive"))
      (node (ref "SW73") (pin "3") (pinfunction "VDD_3") (pintype "passive"))
      (node (ref "SW74") (pin "3") (pinfunction "VDD_3") (pintype "passive"))
      (node (ref "SW75") (pin "3") (pinfunction "VDD_3") (pintype "passive"))
      (node (ref "SW76") (pin "3") (pinfunction "VDD_3") (pintype "passive"))
      (node (ref "SW77") (pin "3") (pinfunction "VDD_3") (pintype "passive"))
      (node (ref "SW78") (pin "3") (pinfunction "VDD_3") (pintype "passive"))
      (node (ref "SW79") (pin "3") (pinfunction "VDD_3") (pintype "passive"))
      (node (ref "SW8") (pin "3") (pinfunction "VDD_3") (pintype "passive"))
      (node (ref "SW80") (pin "3") (pinfunction "VDD_3") (pintype "passive"))
      (node (ref "SW9") (pin "3") (pinfunction "VDD_3") (pintype "passive"))
    )
    (net (code "39") (name "Net-(SW1-DOUT)") (class "Default")
      (node (ref "SW1") (pin "4") (pinfunction "DOUT_4") (pintype "passive"))
      (node (ref "SW2") (pin "6") (pinfunction "DIN_6") (pintype "passive"))
    )
    (net (code "40") (name "Net-(SW2-DOUT)") (class "Default")
      (node (ref "SW2") (pin "4") (pinfunction "DOUT_4") (pintype "passive"))
      (node (ref "SW3") (pin "6") (pinfunction "DIN_6") (pintype "passive"))
    )
    (net (code "41") (name "Net-(SW3-DOUT)") (class "Default")
      (node (ref "SW3") (pin "4") (pinfunction "DOUT_4") (pintype "passive"))
      (node (ref "SW4") (pin "6") (pinfunction "DIN_6") (pintype "passive"))
    )
    (net (code "42") (name "Net-(SW4-DOUT)") (class "Default")
      (node (ref "SW4") (pin "4") (pinfunction "DOUT_4") (pintype "passive"))
      (node (ref "SW5") (pin "6") (pinfunction "DIN_6") (pintype "passive"))
    )
    (net (code "43") (name "Net-(SW5-DOUT)") (class "Default")
      (node (ref "SW5") (pin "4") (pinfunction "DOUT_4") (pintype "passive"))
      (node (ref "SW6") (pin "6") (pinfunction "DIN_6") (pintype "passive"))
    )
    (net (code "44") (name "Net-(SW6-DOUT)") (class "Default")
      (node (ref "SW6") (pin "4") (pinfunction "DOUT_4") (pintype "passive"))
      (node (ref "SW7") (pin "6") (pinfunction "DIN_6") (pintype "passive"))
    )
    (net (code "45") (name "Net-(SW7-DOUT)") (class "Default")
      (node (ref "SW7") (pin "4") (pinfunction "DOUT_4") (pintype "passive"))
      (node (ref "SW8") (pin "6") (pinfunction "DIN_6") (pintype "passive"))
    )
    (net (code "46") (name "Net-(SW8-DOUT)") (class "Default")
      (node (ref "SW8") (pin "4") (pinfunction "DOUT_4") (pintype "passive"))
      (node (ref "SW9") (pin "6") (pinfunction "DIN_6") (pintype "passive"))
    )
    (net (code "47") (name "Net-(SW10-DIN)") (class "Default")
      (node (ref "SW10") (pin "6") (pinfunction "DIN_6") (pintype "passive"))
      (node (ref "SW9") (pin "4") (pinfunction "DOUT_4") (pintype "passive"))
    )
    (net (code "48") (name "Net-(SW10-DOUT)") (class "Default")
      (node (ref "SW10") (pin "4") (pinfunction "DOUT_4") (pintype "passive"))
      (node (ref "SW11") (pin "6") (pinfunction "DIN_6") (pintype "passive"))
    )
    (net (code "49") (name "Net-(SW11-DOUT)") (class "Default")
      (node (ref "SW11") (pin "4") (pinfunction "DOUT_4") (pintype "passive"))
      (node (ref "SW12") (pin "6") (pinfunction "DIN_6") (pintype "passive"))
    )
    (net (code "50") (name "Net-(SW12-DOUT)") (class "Default")
      (node (ref "SW12") (pin "4") (pinfunction "DOUT_4") (pintype "passive"))
      (node (ref "SW13") (pin "6") (pinfunction "DIN_6") (pintype "passive"))
    )
    (net (code "51") (name "Net-(SW14-DOUT)") (class "Default")
      (node (ref "SW14") (pin "4") (pinfunction "DOUT_4") (pintype "passive"))
      (node (ref "SW15") (pin "6") (pinfunction "DIN_6") (pintype "passive"))
    )
    (net (code "52") (name "Net-(SW15-DOUT)") (class "Default")
      (node (ref "SW15") (pin "4") (pinfunction "DOUT_4") (pintype "passive"))
      (node (ref "SW16") (pin "6") (pinfunction "DIN_6") (pintype "passive"))
    )
    (net (code "53") (name "Net-(SW16-DOUT)") (class "Default")
      (node (ref "SW16") (pin "4") (pinfunction "DOUT_4") (pintype "passive"))
      (node (ref "SW17") (pin "6") (pinfunction "DIN_6") (pintype "passive"))
    )
    (net (code "54") (name "Net-(SW17-DOUT)") (class "Default")
      (node (ref "SW17") (pin "4") (pinfunction "DOUT_4") (pintype "passive"))
      (node (ref "SW18") (pin "6") (pinfunction "DIN_6") (pintype "passive"))
    )
    (net (code "55") (name "Net-(SW18-DOUT)") (class "Default")
      (node (ref "SW18") (pin "4") (pinfunction "DOUT_4") (pintype "passive"))
      (node (ref "SW19") (pin "6") (pinfunction "DIN_6") (pintype "passive"))
    )
    (net (code "56") (name "Net-(SW19-DOUT)") (class "Default")
      (node (ref "SW19") (pin "4") (pinfunction "DOUT_4") (pintype "passive"))
      (node (ref "SW20") (pin "6") (pinfunction "DIN_6") (pintype "passive"))
    )
    (net (code "57") (name "Net-(SW20-DOUT)") (class "Default")
      (node (ref "SW20") (pin "4") (pinfunction "DOUT_4") (pintype "passive"))
      (node (ref "SW21") (pin "6") (pinfunction "DIN_6") (pintype "passive"))
    )
    (net (code "58") (name "Net-(SW21-DOUT)") (class "Default")
      (node (ref "SW21") (pin "4") (pinfunction "DOUT_4") (pintype "passive"))
      (node (ref "SW22") (pin "6") (pinfunction "DIN_6") (pintype "passive"))
    )
    (net (code "59") (name "Net-(SW22-DOUT)") (class "Default")
      (node (ref "SW22") (pin "4") (pinfunction "DOUT_4") (pintype "passive"))
      (node (ref "SW23") (pin "6") (pinfunction "DIN_6") (pintype "passive"))
    )
    (net (code "60") (name "Net-(SW23-DOUT)") (class "Default")
      (node (ref "SW23") (pin "4") (pinfunction "DOUT_4") (pintype "passive"))
      (node (ref "SW24") (pin "6") (pinfunction "DIN_6") (pintype "passive"))
    )
    (net (code "61") (name "Net-(SW24-DOUT)") (class "Default")
      (node (ref "SW24") (pin "4") (pinfunction "DOUT_4") (pintype "passive"))
      (node (ref "SW25") (pin "6") (pinfunction "DIN_6") (pintype "passive"))
    )
    (net (code "62") (name "Net-(SW25-DOUT)") (class "Default")
      (node (ref "SW25") (pin "4") (pinfunction "DOUT_4") (pintype "passive"))
      (node (ref "SW26") (pin "6") (pinfunction "DIN_6") (pintype "passive"))
    )
    (net (code "63") (name "Net-(SW26-DOUT)") (class "Default")
      (node (ref "SW26") (pin "4") (pinfunction "DOUT_4") (pintype "passive"))
      (node (ref "SW27") (pin "6") (pinfunction "DIN_6") (pintype "passive"))
    )
    (net (code "64") (name "Net-(SW27-DOUT)") (class "Default")
      (node (ref "R1") (pin "1") (pinfunction "1_1") (pintype "passive"))
      (node (ref "SW27") (pin "4") (pinfunction "DOUT_4") (pintype "passive"))
    )
    (net (code "65") (name "Net-(SW28-DOUT)") (class "Default")
      (node (ref "SW28") (pin "4") (pinfunction "DOUT_4") (pintype "passive"))
      (node (ref "SW29") (pin "6") (pinfunction "DIN_6") (pintype "passive"))
    )
    (net (code "66") (name "Net-(SW29-DOUT)") (class "Default")
      (node (ref "SW29") (pin "4") (pinfunction "DOUT_4") (pintype "passive"))
      (node (ref "SW30") (pin "6") (pinfunction "DIN_6") (pintype "passive"))
    )
    (net (code "67") (name "Net-(SW30-DOUT)") (class "Default")
      (node (ref "SW30") (pin "4") (pinfunction "DOUT_4") (pintype "passive"))
      (node (ref "SW31") (pin "6") (pinfunction "DIN_6") (pintype "passive"))
    )
    (net (code "68") (name "Net-(SW31-DOUT)") (class "Default")
      (node (ref "SW31") (pin "4") (pinfunction "DOUT_4") (pintype "passive"))
      (node (ref "SW32") (pin "6") (pinfunction "DIN_6") (pintype "passive"))
    )
    (net (code "69") (name "Net-(SW32-DOUT)") (class "Default")
      (node (ref "SW32") (pin "4") (pinfunction "DOUT_4") (pintype "passive"))
      (node (ref "SW33") (pin "6") (pinfunction "DIN_6") (pintype "passive"))
    )
    (net (code "70") (name "Net-(SW33-DOUT)") (class "Default")
      (node (ref "SW33") (pin "4") (pinfunction "DOUT_4") (pintype "passive"))
      (node (ref "SW34") (pin "6") (pinfunction "DIN_6") (pintype "passive"))
    )
    (net (code "71") (name "Net-(SW34-DOUT)") (class "Default")
      (node (ref "SW34") (pin "4") (pinfunction "DOUT_4") (pintype "passive"))
      (node (ref "SW35") (pin "6") (pinfunction "DIN_6") (pintype "passive"))
    )
    (net (code "72") (name "Net-(SW35-DOUT)") (class "Default")
      (node (ref "SW35") (pin "4") (pinfunction "DOUT_4") (pintype "passive"))
      (node (ref "SW36") (pin "6") (pinfunction "DIN_6") (pintype "passive"))
    )
    (net (code "73") (name "Net-(SW36-DOUT)") (class "Default")
      (node (ref "SW36") (pin "4") (pinfunction "DOUT_4") (pintype "passive"))
      (node (ref "SW37") (pin "6") (pinfunction "DIN_6") (pintype "passive"))
    )
    (net (code "74") (name "Net-(SW37-DOUT)") (class "Default")
      (node (ref "SW37") (pin "4") (pinfunction "DOUT_4") (pintype "passive"))
      (node (ref "SW38") (pin "6") (pinfunction "DIN_6") (pintype "passive"))
    )
    (net (code "75") (name "Net-(SW38-DOUT)") (class "Default")
      (node (ref "SW38") (pin "4") (pinfunction "DOUT_4") (pintype "passive"))
      (node (ref "SW39") (pin "6") (pinfunction "DIN_6") (pintype "passive"))
    )
    (net (code "76") (name "Net-(SW39-DOUT)") (class "Default")
      (node (ref "SW39") (pin "4") (pinfunction "DOUT_4") (pintype "passive"))
      (node (ref "SW40") (pin "6") (pinfunction "DIN_6") (pintype "passive"))
    )
    (net (code "77") (name "Net-(SW40-DOUT)") (class "Default")
      (node (ref "SW40") (pin "4") (pinfunction "DOUT_4") (pintype "passive"))
      (node (ref "SW41") (pin "6") (pinfunction "DIN_6") (pintype "passive"))
    )
    (net (code "78") (name "Net-(SW42-DOUT)") (class "Default")
      (node (ref "SW42") (pin "4") (pinfunction "DOUT_4") (pintype "passive"))
      (node (ref "SW43") (pin "6") (pinfunction "DIN_6") (pintype "passive"))
    )
    (net (code "79") (name "Net-(SW43-DOUT)") (class "Default")
      (node (ref "SW43") (pin "4") (pinfunction "DOUT_4") (pintype "passive"))
      (node (ref "SW44") (pin "6") (pinfunction "DIN_6") (pintype "passive"))
    )
    (net (code "80") (name "Net-(SW44-DOUT)") (class "Default")
      (node (ref "SW44") (pin "4") (pinfunction "DOUT_4") (pintype "passive"))
      (node (ref "SW45") (pin "6") (pinfunction "DIN_6") (pintype "passive"))
    )
    (net (code "81") (name "Net-(SW45-DOUT)") (class "Default")
      (node (ref "SW45") (pin "4") (pinfunction "DOUT_4") (pintype "passive"))
      (node (ref "SW46") (pin "6") (pinfunction "DIN_6") (pintype "passive"))
    )
    (net (code "82") (name "Net-(SW46-DOUT)") (class "Default")
      (node (ref "SW46") (pin "4") (pinfunction "DOUT_4") (pintype "passive"))
      (node (ref "SW47") (pin "6") (pinfunction "DIN_6") (pintype "passive"))
    )
    (net (code "83") (name "Net-(SW47-DOUT)") (class "Default")
      (node (ref "SW47") (pin "4") (pinfunction "DOUT_4") (pintype "passive"))
      (node (ref "SW48") (pin "6") (pinfunction "DIN_6") (pintype "passive"))
    )
    (net (code "84") (name "Net-(SW48-DOUT)") (class "Default")
      (node (ref "SW48") (pin "4") (pinfunction "DOUT_4") (pintype "passive"))
      (node (ref "SW49") (pin "6") (pinfunction "DIN_6") (pintype "passive"))
    )
    (net (code "85") (name "Net-(SW49-DOUT)") (class "Default")
      (node (ref "SW49") (pin "4") (pinfunction "DOUT_4") (pintype "passive"))
      (node (ref "SW50") (pin "6") (pinfunction "DIN_6") (pintype "passive"))
    )
    (net (code "86") (name "Net-(SW50-DOUT)") (class "Default")
      (node (ref "SW50") (pin "4") (pinfunction "DOUT_4") (pintype "passive"))
      (node (ref "SW51") (pin "6") (pinfunction "DIN_6") (pintype "passive"))
    )
    (net (code "87") (name "Net-(SW51-DOUT)") (class "Default")
      (node (ref "SW51") (pin "4") (pinfunction "DOUT_4") (pintype "passive"))
      (node (ref "SW52") (pin "6") (pinfunction "DIN_6") (pintype "passive"))
    )
    (net (code "88") (name "Net-(SW52-DOUT)") (class "Default")
      (node (ref "SW52") (pin "4") (pinfunction "DOUT_4") (pintype "passive"))
      (node (ref "SW53") (pin "6") (pinfunction "DIN_6") (pintype "passive"))
    )
    (net (code "89") (name "Net-(SW53-DOUT)") (class "Default")
      (node (ref "SW53") (pin "4") (pinfunction "DOUT_4") (pintype "passive"))
      (node (ref "SW54") (pin "6") (pinfunction "DIN_6") (pintype "passive"))
    )
    (net (code "90") (name "Net-(SW54-DOUT)") (class "Default")
      (node (ref "SW54") (pin "4") (pinfunction "DOUT_4") (pintype "passive"))
      (node (ref "SW55") (pin "6") (pinfunction "DIN_6") (pintype "passive"))
    )
    (net (code "91") (name "Net-(SW55-DOUT)") (class "Default")
      (node (ref "R2") (pin "1") (pinfunction "1_1") (pintype "passive"))
      (node (ref "SW55") (pin "4") (pinfunction "DOUT_4") (pintype "passive"))
    )
    (net (code "92") (name "Net-(SW56-DOUT)") (class "Default")
      (node (ref "SW56") (pin "4") (pinfunction "DOUT_4") (pintype "passive"))
      (node (ref "SW57") (pin "6") (pinfunction "DIN_6") (pintype "passive"))
    )
    (net (code "93") (name "Net-(SW57-DOUT)") (class "Default")
      (node (ref "SW57") (pin "4") (pinfunction "DOUT_4") (pintype "passive"))
      (node (ref "SW58") (pin "6") (pinfunction "DIN_6") (pintype "passive"))
    )
    (net (code "94") (name "Net-(SW58-DOUT)") (class "Default")
      (node (ref "SW58") (pin "4") (pinfunction "DOUT_4") (pintype "passive"))
      (node (ref "SW59") (pin "6") (pinfunction "DIN_6") (pintype "passive"))
    )
    (net (code "95") (name "Net-(SW59-DOUT)") (class "Default")
      (node (ref "SW59") (pin "4") (pinfunction "DOUT_4") (pintype "passive"))
      (node (ref "SW60") (pin "6") (pinfunction "DIN_6") (pintype "passive"))
    )
    (net (code "96") (name "Net-(SW60-DOUT)") (class "Default")
      (node (ref "SW60") (pin "4") (pinfunction "DOUT_4") (pintype "passive"))
      (node (ref "SW61") (pin "6") (pinfunction "DIN_6") (pintype "passive"))
    )
    (net (code "97") (name "Net-(SW61-DOUT)") (class "Default")
      (node (ref "SW61") (pin "4") (pinfunction "DOUT_4") (pintype "passive"))
      (node (ref "SW62") (pin "6") (pinfunction "DIN_6") (pintype "passive"))
    )
    (net (code "98") (name "Net-(SW62-DOUT)") (class "Default")
      (node (ref "SW62") (pin "4") (pinfunction "DOUT_4") (pintype "passive"))
      (node (ref "SW63") (pin "6") (pinfunction "DIN_6") (pintype "passive"))
    )
    (net (code "99") (name "Net-(SW63-DOUT)") (class "Default")
      (node (ref "SW63") (pin "4") (pinfunction "DOUT_4") (pintype "passive"))
      (node (ref "SW64") (pin "6") (pinfunction "DIN_6") (pintype "passive"))
    )
    (net (code "100") (name "Net-(SW64-DOUT)") (class "Default")
      (node (ref "SW64") (pin "4") (pinfunction "DOUT_4") (pintype "passive"))
      (node (ref "SW65") (pin "6") (pinfunction "DIN_6") (pintype "passive"))
    )
    (net (code "101") (name "Net-(SW65-DOUT)") (class "Default")
      (node (ref "SW65") (pin "4") (pinfunction "DOUT_4") (pintype "passive"))
      (node (ref "SW66") (pin "6") (pinfunction "DIN_6") (pintype "passive"))
    )
    (net (code "102") (name "Net-(SW66-DOUT)") (class "Default")
      (node (ref "SW66") (pin "4") (pinfunction "DOUT_4") (pintype "passive"))
      (node (ref "SW67") (pin "6") (pinfunction "DIN_6") (pintype "passive"))
    )
    (net (code "103") (name "Net-(SW67-DOUT)") (class "Default")
      (node (ref "SW67") (pin "4") (pinfunction "DOUT_4") (pintype "passive"))
      (node (ref "SW68") (pin "6") (pinfunction "DIN_6") (pintype "passive"))
    )
    (net (code "104") (name "Net-(SW69-DOUT)") (class "Default")
      (node (ref "SW69") (pin "4") (pinfunction "DOUT_4") (pintype "passive"))
      (node (ref "SW70") (pin "6") (pinfunction "DIN_6") (pintype "passive"))
    )
    (net (code "105") (name "Net-(SW70-DOUT)") (class "Default")
      (node (ref "SW70") (pin "4") (pinfunction "DOUT_4") (pintype "passive"))
      (node (ref "SW71") (pin "6") (pinfunction "DIN_6") (pintype "passive"))
    )
    (net (code "106") (name "Net-(SW71-DOUT)") (class "Default")
      (node (ref "SW71") (pin "4") (pinfunction "DOUT_4") (pintype "passive"))
      (node (ref "SW72") (pin "6") (pinfunction "DIN_6") (pintype "passive"))
    )
    (net (code "107") (name "Net-(SW72-DOUT)") (class "Default")
      (node (ref "SW72") (pin "4") (pinfunction "DOUT_4") (pintype "passive"))
      (node (ref "SW73") (pin "6") (pinfunction "DIN_6") (pintype "passive"))
    )
    (net (code "108") (name "Net-(SW73-DOUT)") (class "Default")
      (node (ref "SW73") (pin "4") (pinfunction "DOUT_4") (pintype "passive"))
      (node (ref "SW74") (pin "6") (pinfunction "DIN_6") (pintype "passive"))
    )
    (net (code "109") (name "Net-(SW74-DOUT)") (class "Default")
      (node (ref "SW74") (pin "4") (pinfunction "DOUT_4") (pintype "passive"))
      (node (ref "SW75") (pin "6") (pinfunction "DIN_6") (pintype "passive"))
    )
    (net (code "110") (name "Net-(SW75-DOUT)") (class "Default")
      (node (ref "SW75") (pin "4") (pinfunction "DOUT_4") (pintype "passive"))
      (node (ref "SW76") (pin "6") (pinfunction "DIN_6") (pintype "passive"))
    )
    (net (code "111") (name "Net-(SW76-DOUT)") (class "Default")
      (node (ref "SW76") (pin "4") (pinfunction "DOUT_4") (pintype "passive"))
      (node (ref "SW77") (pin "6") (pinfunction "DIN_6") (pintype "passive"))
    )
    (net (code "112") (name "Net-(SW77-DOUT)") (class "Default")
      (node (ref "SW77") (pin "4") (pinfunction "DOUT_4") (pintype "passive"))
      (node (ref "SW78") (pin "6") (pinfunction "DIN_6") (pintype "passive"))
    )
    (net (code "113") (name "Net-(SW78-DOUT)") (class "Default")
      (node (ref "SW78") (pin "4") (pinfunction "DOUT_4") (pintype "passive"))
      (node (ref "SW79") (pin "6") (pinfunction "DIN_6") (pintype "passive"))
    )
    (net (code "114") (name "Net-(SW79-DOUT)") (class "Default")
      (node (ref "SW79") (pin "4") (pinfunction "DOUT_4") (pintype "passive"))
      (node (ref "SW80") (pin "6") (pinfunction "DIN_6") (pintype "passive"))
    )
    (net (code "115") (name "Net-(SW80-DOUT)") (class "Default")
      (node (ref "R3") (pin "1") (pinfunction "1_1") (pintype "passive"))
      (node (ref "SW80") (pin "4") (pinfunction "DOUT_4") (pintype "passive"))
    )
    (net (code "116") (name "WS2812_CTR1") (class "Default")
      (node (ref "5") (pin "9") (pinfunction "9_9") (pintype "passive"))
      (node (ref "SW1") (pin "6") (pinfunction "DIN_6") (pintype "passive"))
    )
    (net (code "117") (name "WS2812_CTR2") (class "Default")
      (node (ref "5") (pin "8") (pinfunction "8_8") (pintype "passive"))
      (node (ref "SW28") (pin "6") (pinfunction "DIN_6") (pintype "passive"))
    )
    (net (code "118") (name "WS2812_CTR3") (class "Default")
      (node (ref "5") (pin "7") (pinfunction "7_7") (pintype "passive"))
      (node (ref "SW56") (pin "6") (pinfunction "DIN_6") (pintype "passive"))
    )
    (net (code "119") (name "unconnected-(R1-Pad2)") (class "Default")
      (node (ref "R1") (pin "2") (pinfunction "2_2") (pintype "passive+no_connect"))
    )
    (net (code "120") (name "unconnected-(R2-Pad2)") (class "Default")
      (node (ref "R2") (pin "2") (pinfunction "2_2") (pintype "passive+no_connect"))
    )
    (net (code "121") (name "unconnected-(R3-Pad2)") (class "Default")
      (node (ref "R3") (pin "2") (pinfunction "2_2") (pintype "passive+no_connect"))
    )
    (net (code "122") (name "unconnected-(U2-GND-Pad7)") (class "Default")
      (node (ref "U2") (pin "7") (pinfunction "GND_7") (pintype "passive+no_connect"))
    )
    (net (code "123") (name "unconnected-(U2-NC-Pad8)") (class "Default")
      (node (ref "U2") (pin "8") (pinfunction "NC_8") (pintype "passive+no_connect"))
    )
    (net (code "124") (name "unconnected-(U2-NC-Pad8)_1") (class "Default")
      (node (ref "U2") (pin "8") (pinfunction "NC_8") (pintype "passive+no_connect"))
    )
  )
)
